# Index_Registers_-_1_1.net
KiCad netlist of a schematic drawn in EAGLE
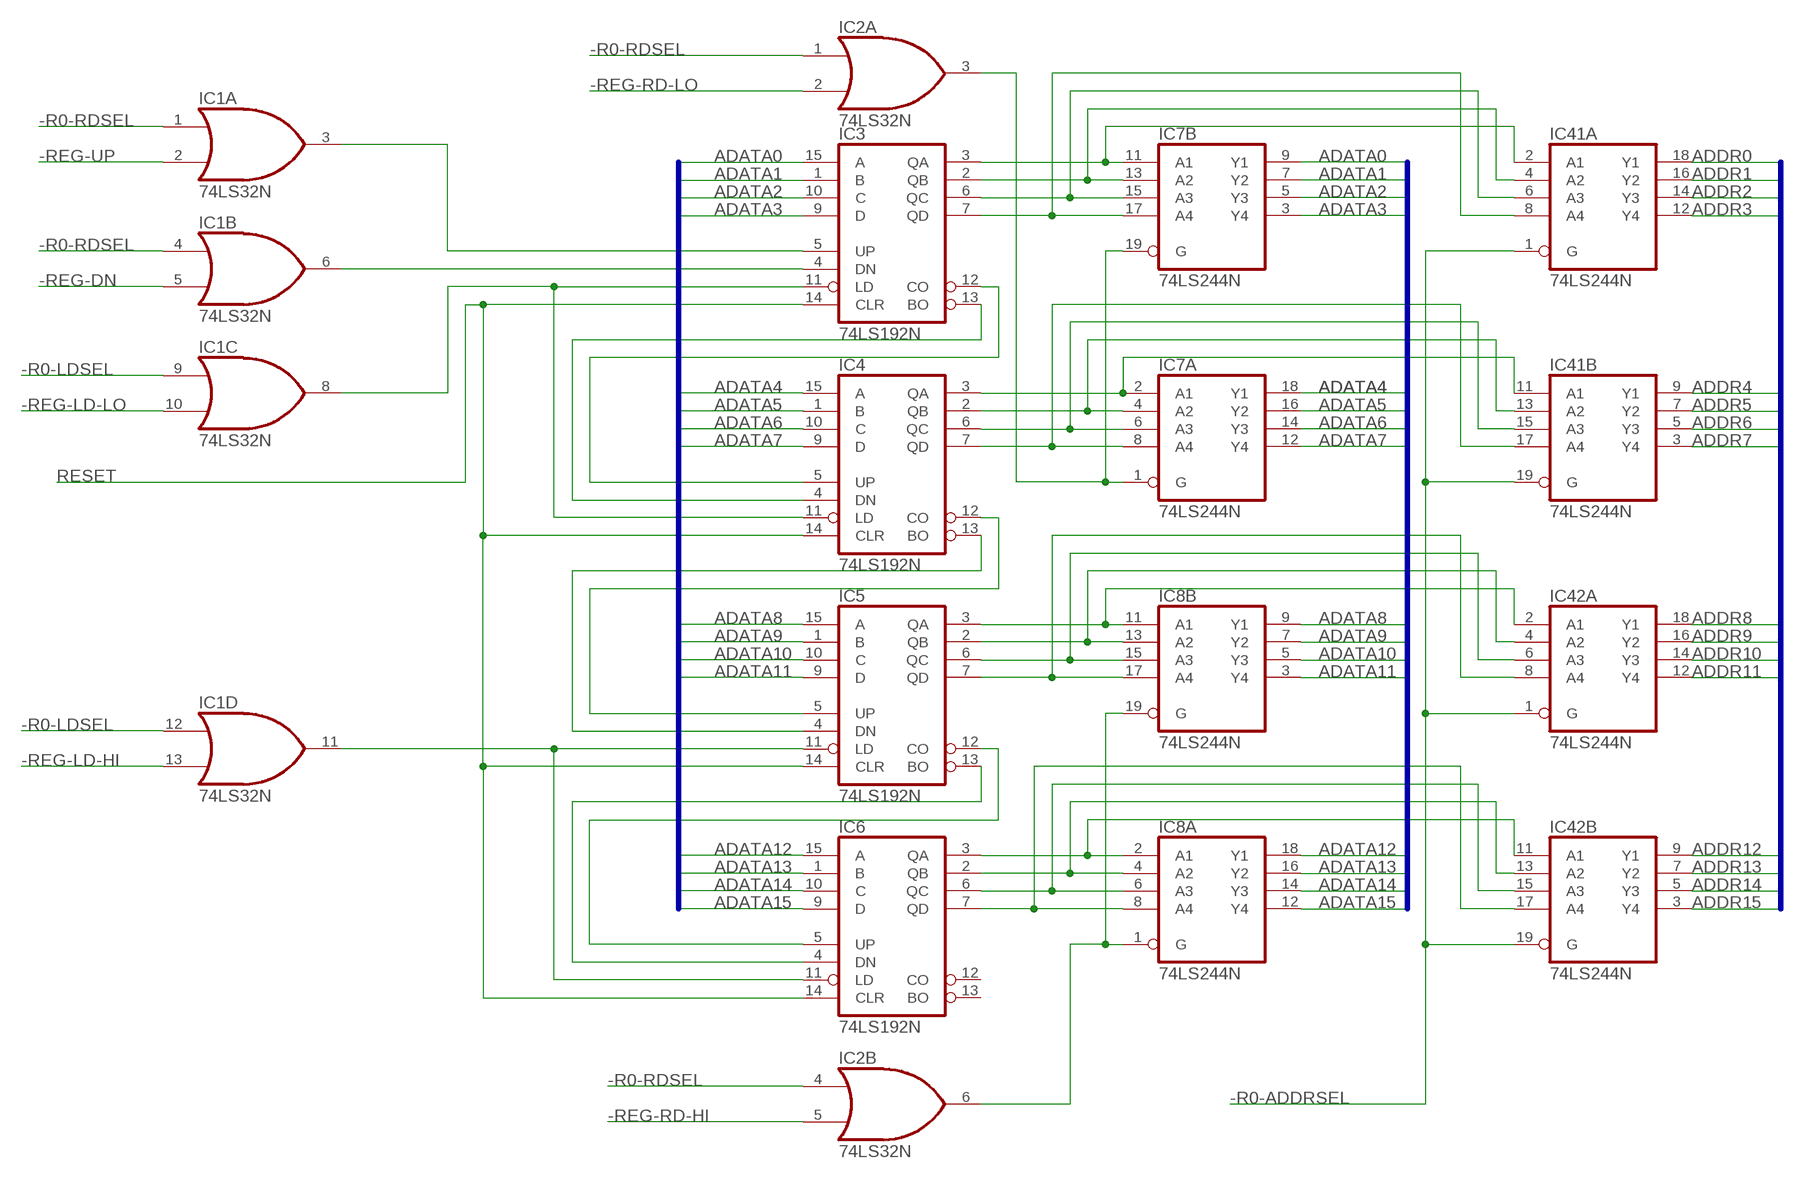
[diagram p0: schematic, sheet 1]
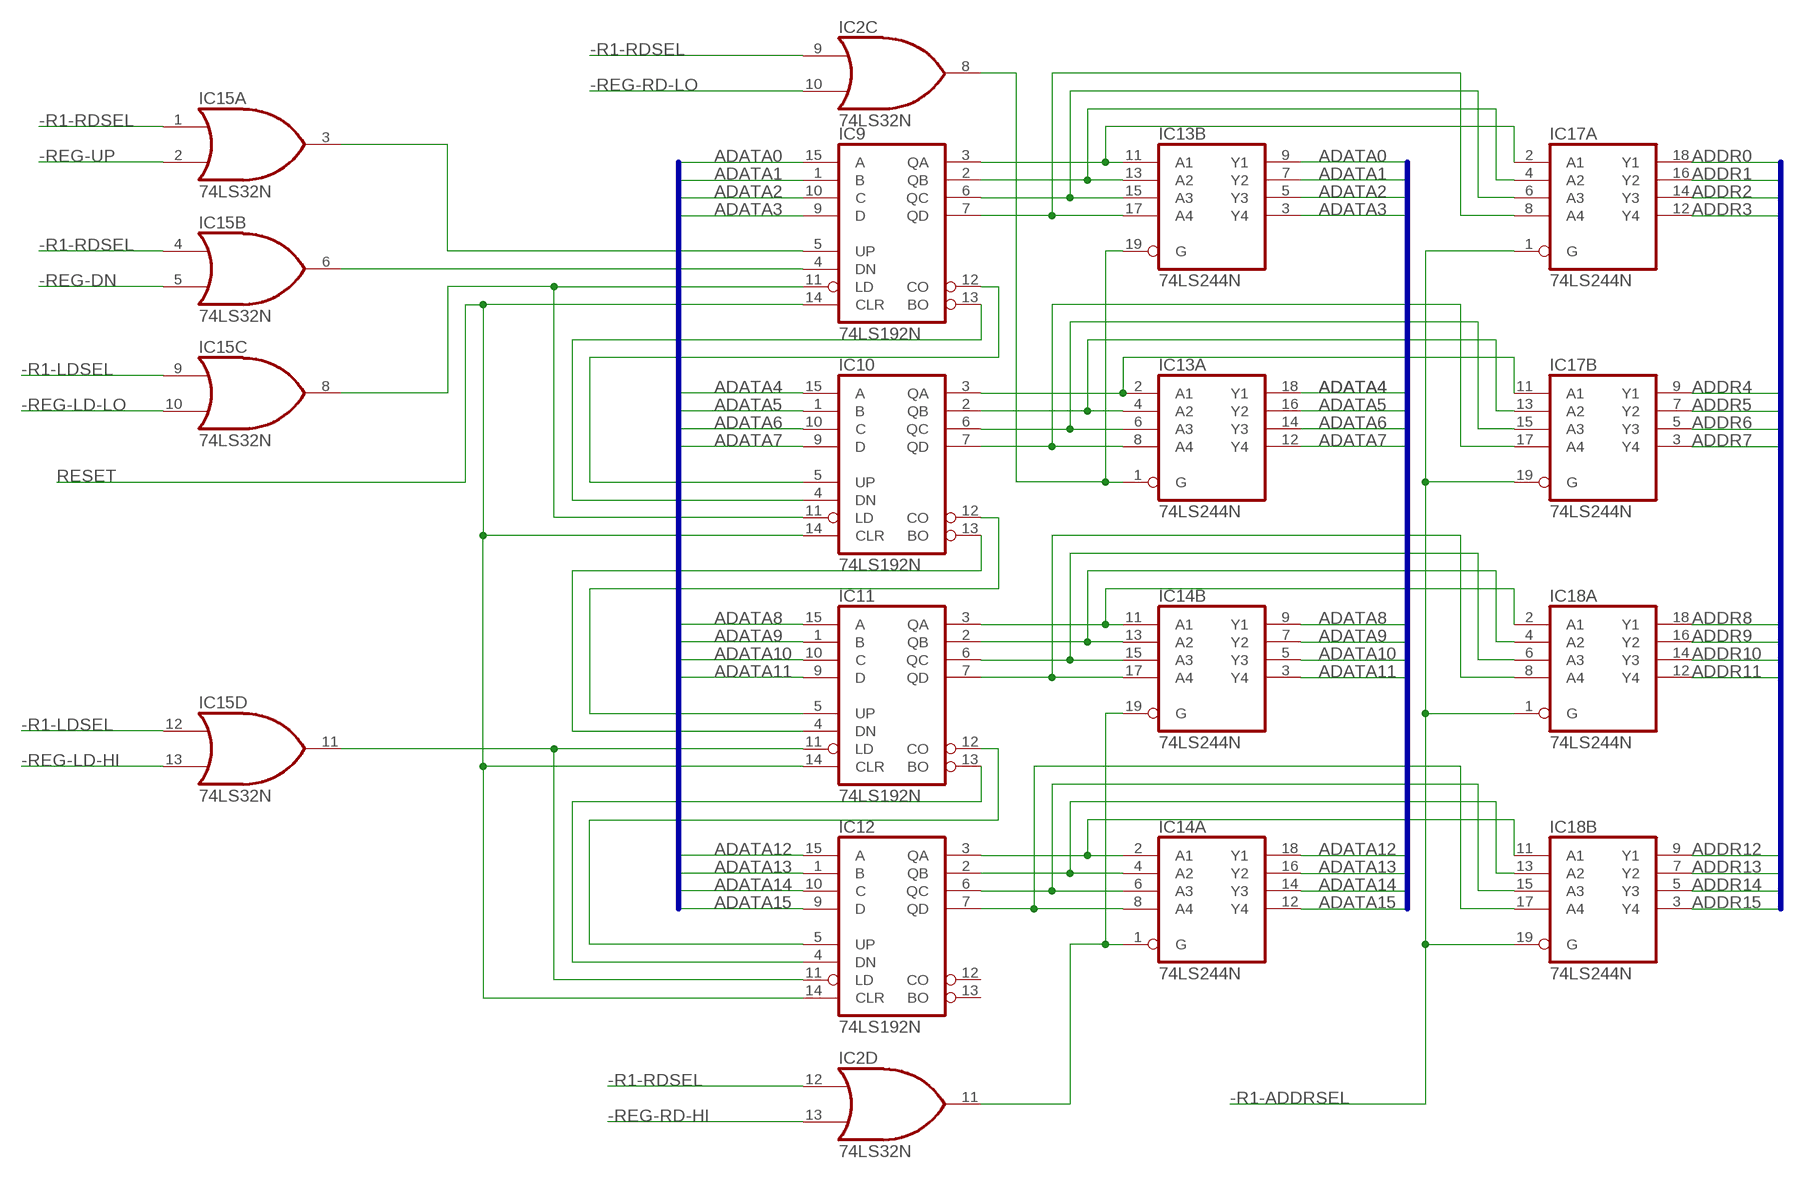
[diagram p1: schematic, sheet 2]
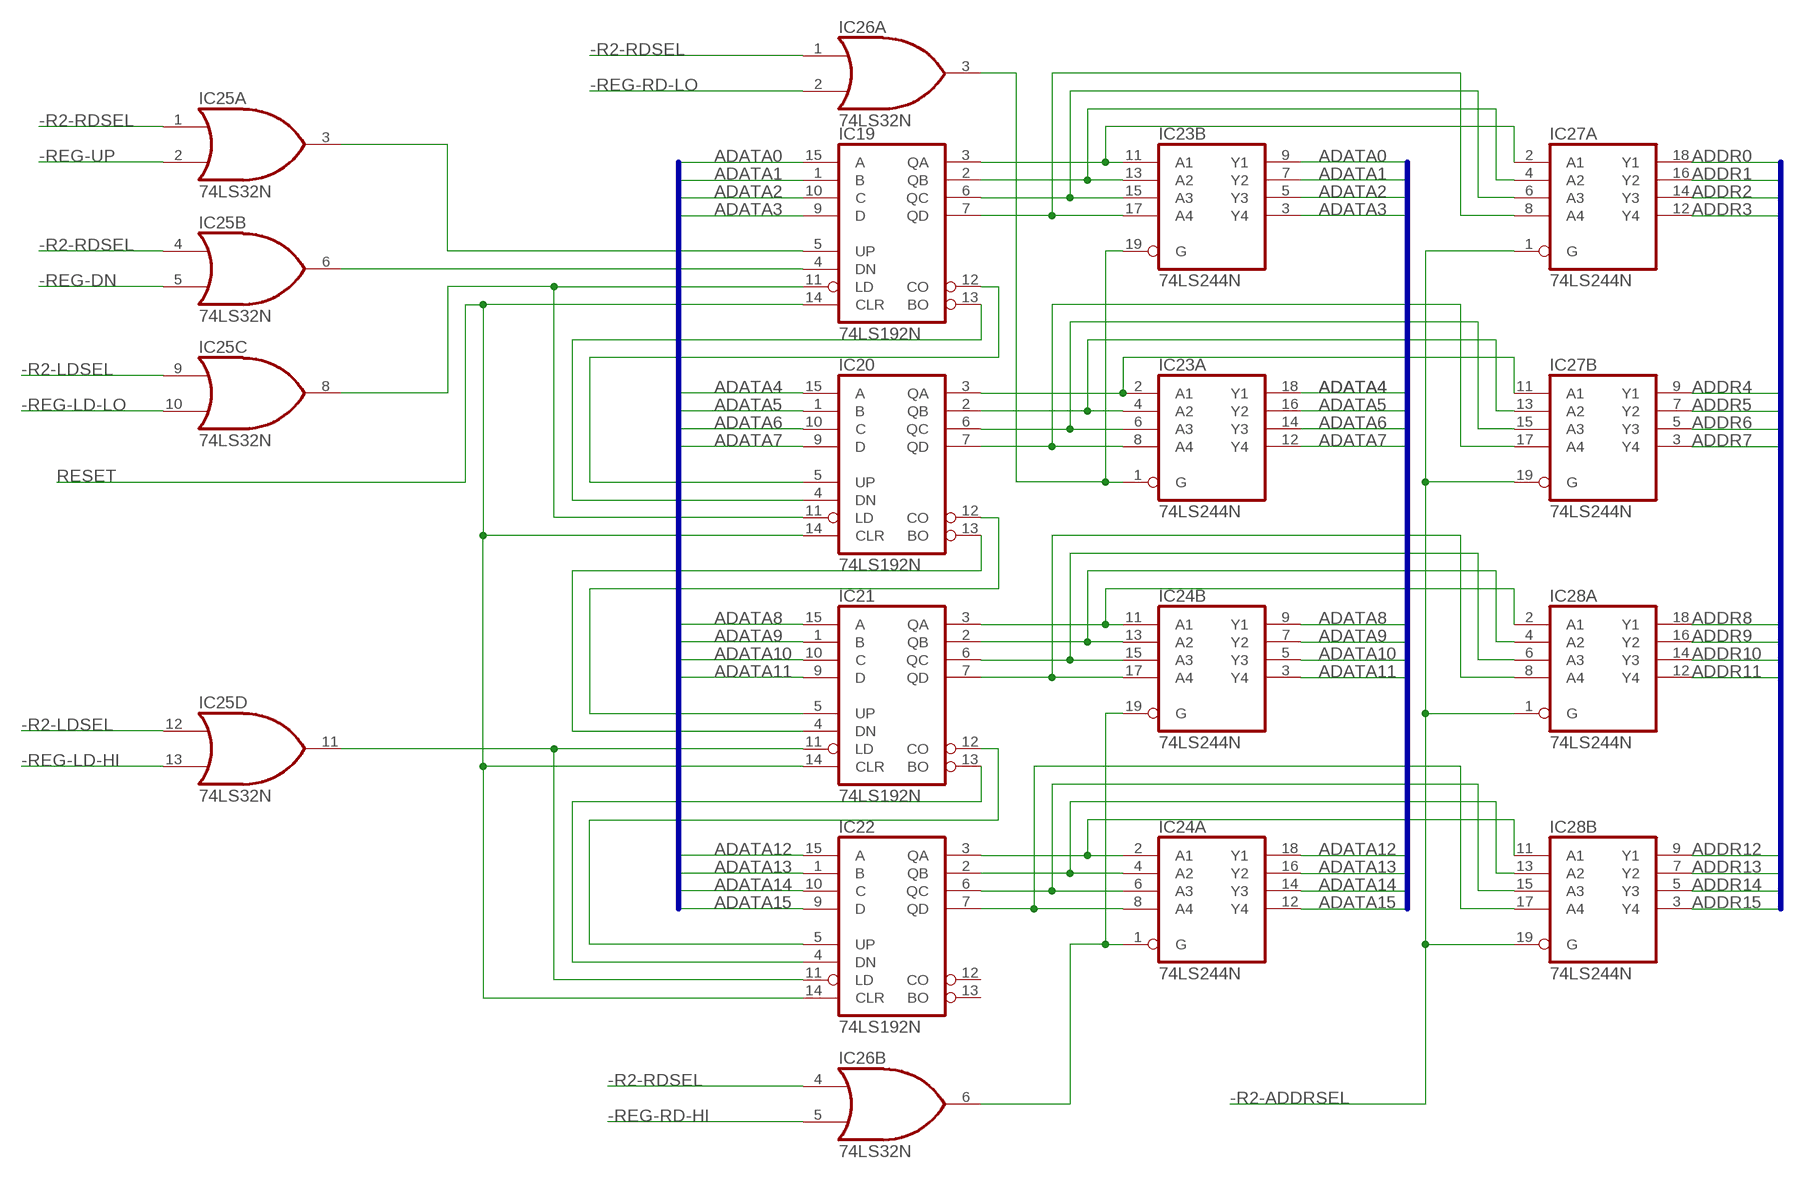
[diagram p2: schematic, sheet 3]
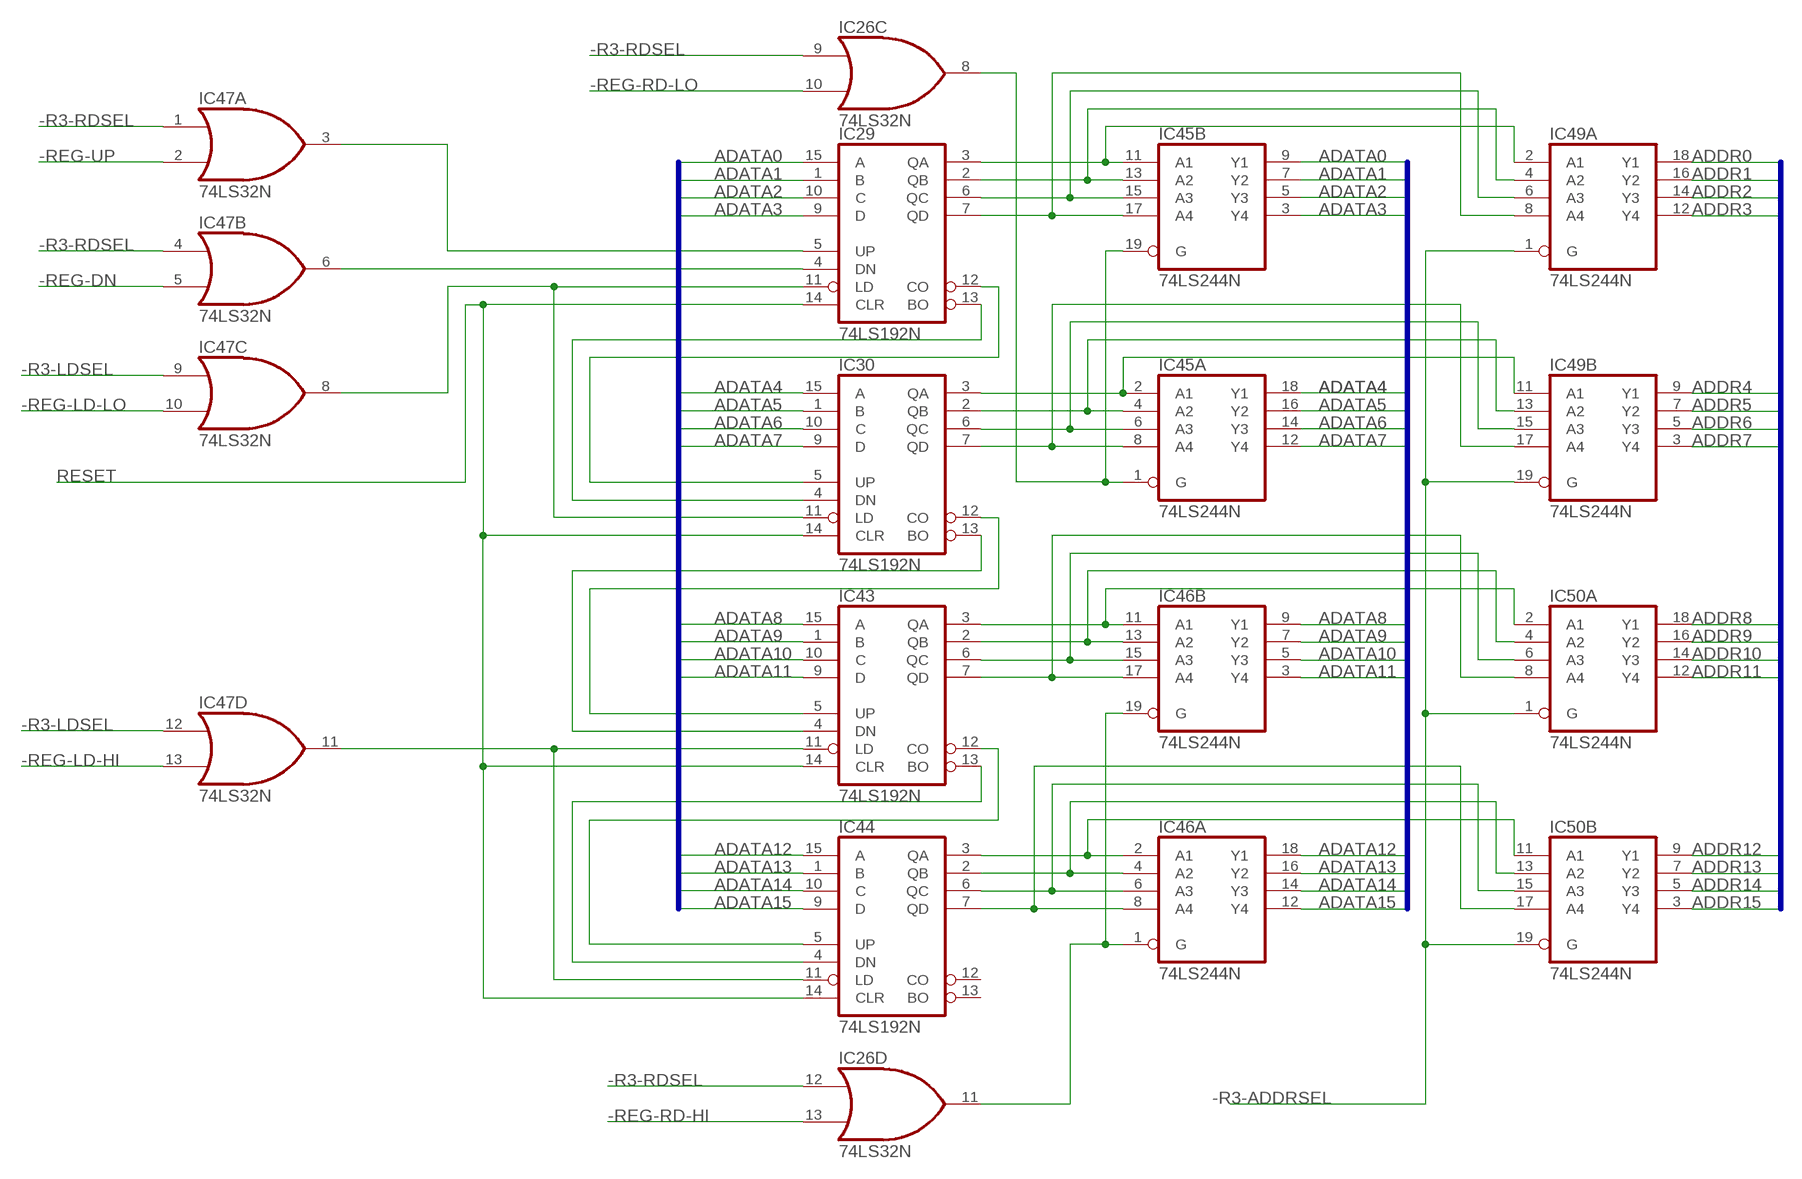
[diagram p3: schematic, sheet 4]
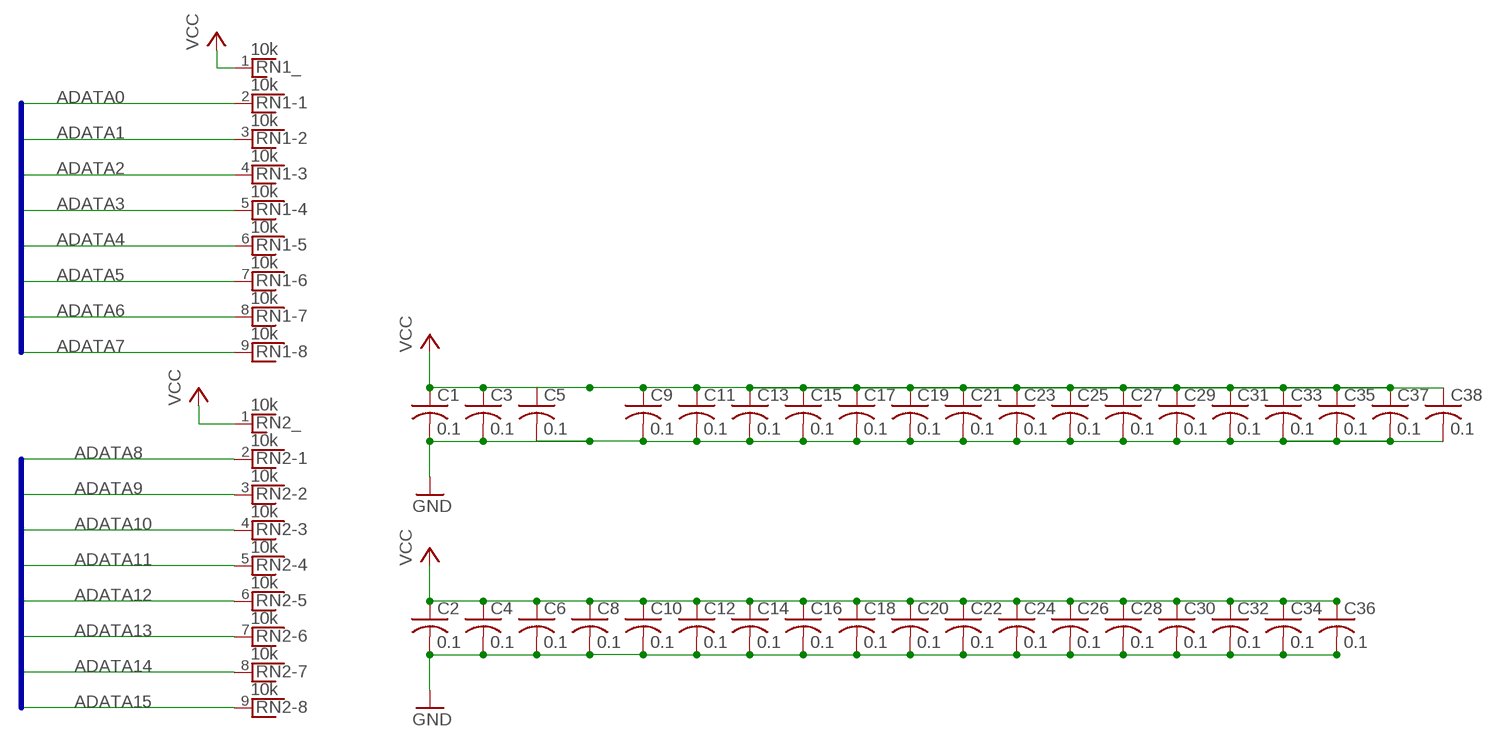
[diagram p4: schematic, sheet 5]
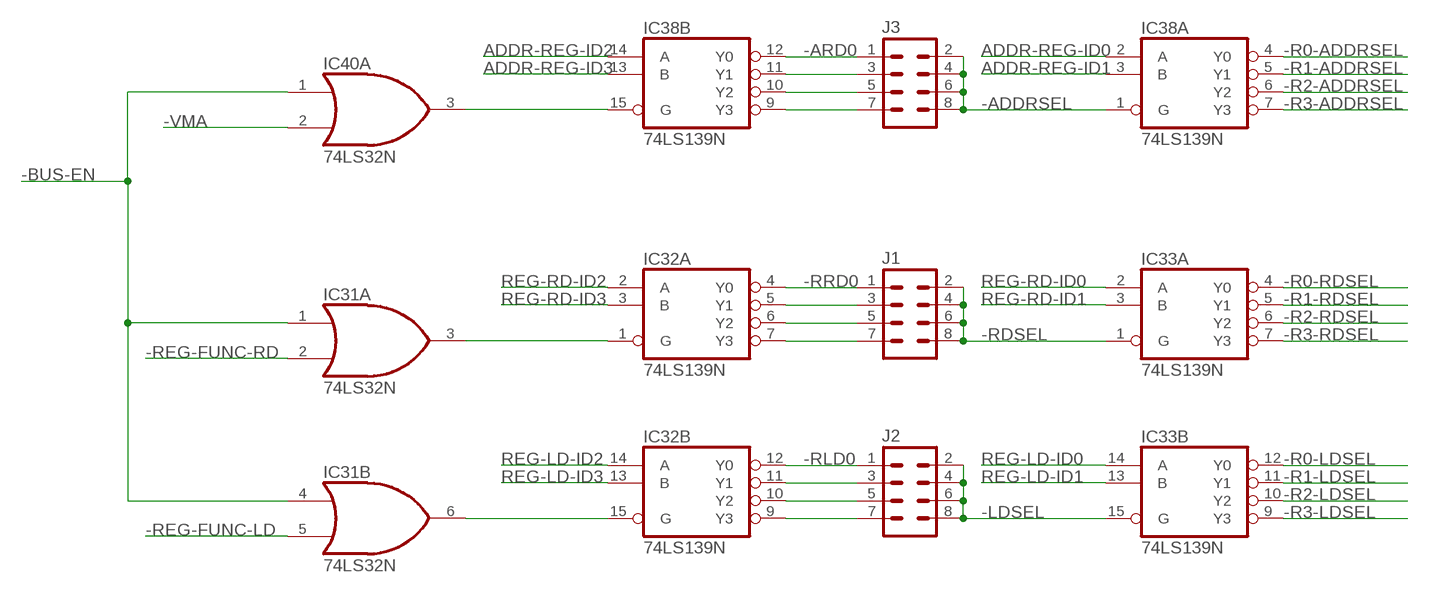
[diagram p5: schematic, sheet 6]
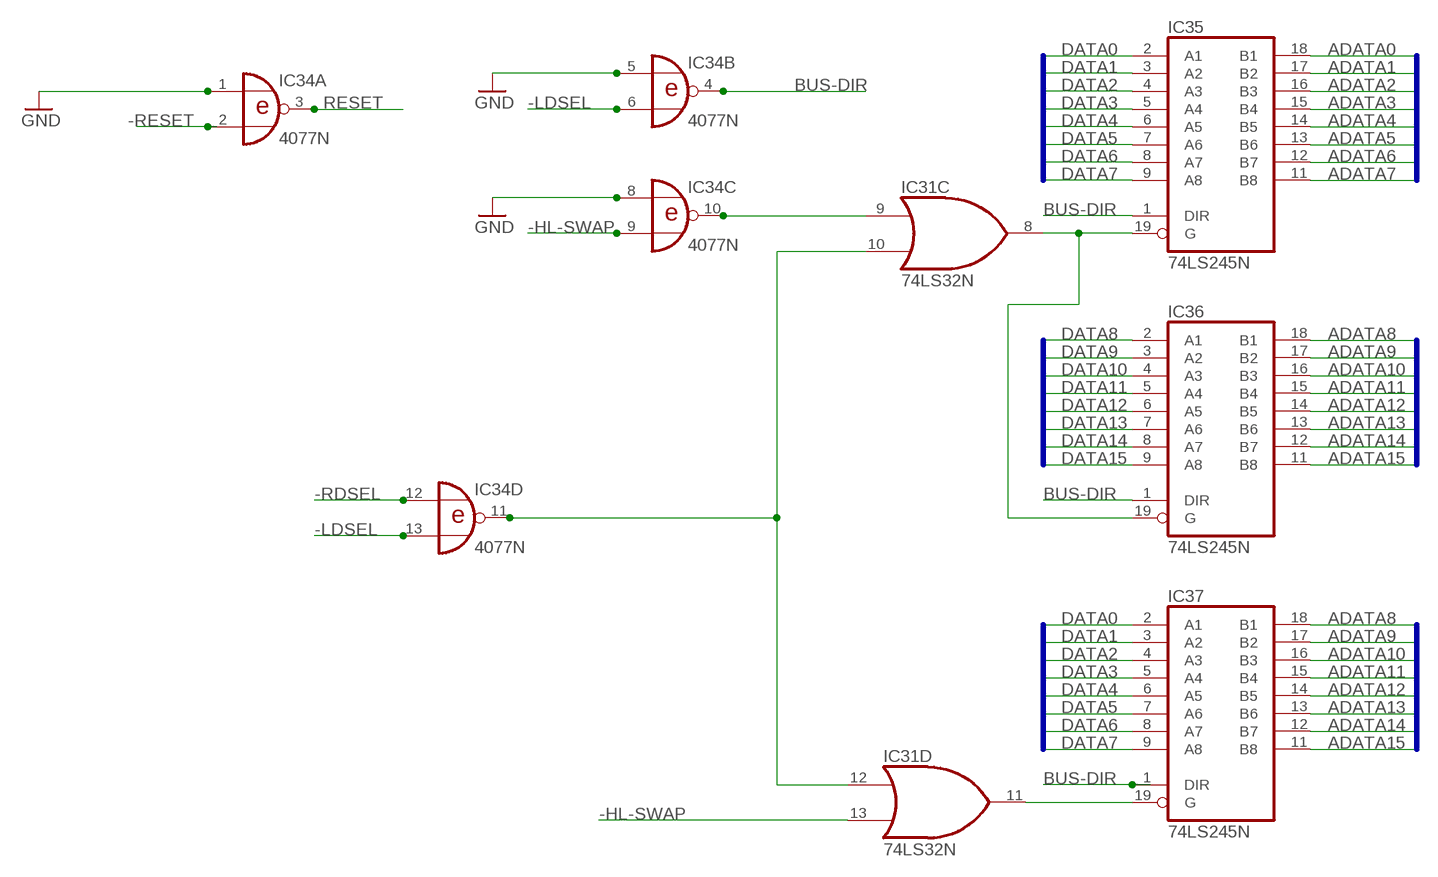
[diagram p6: schematic, sheet 7]
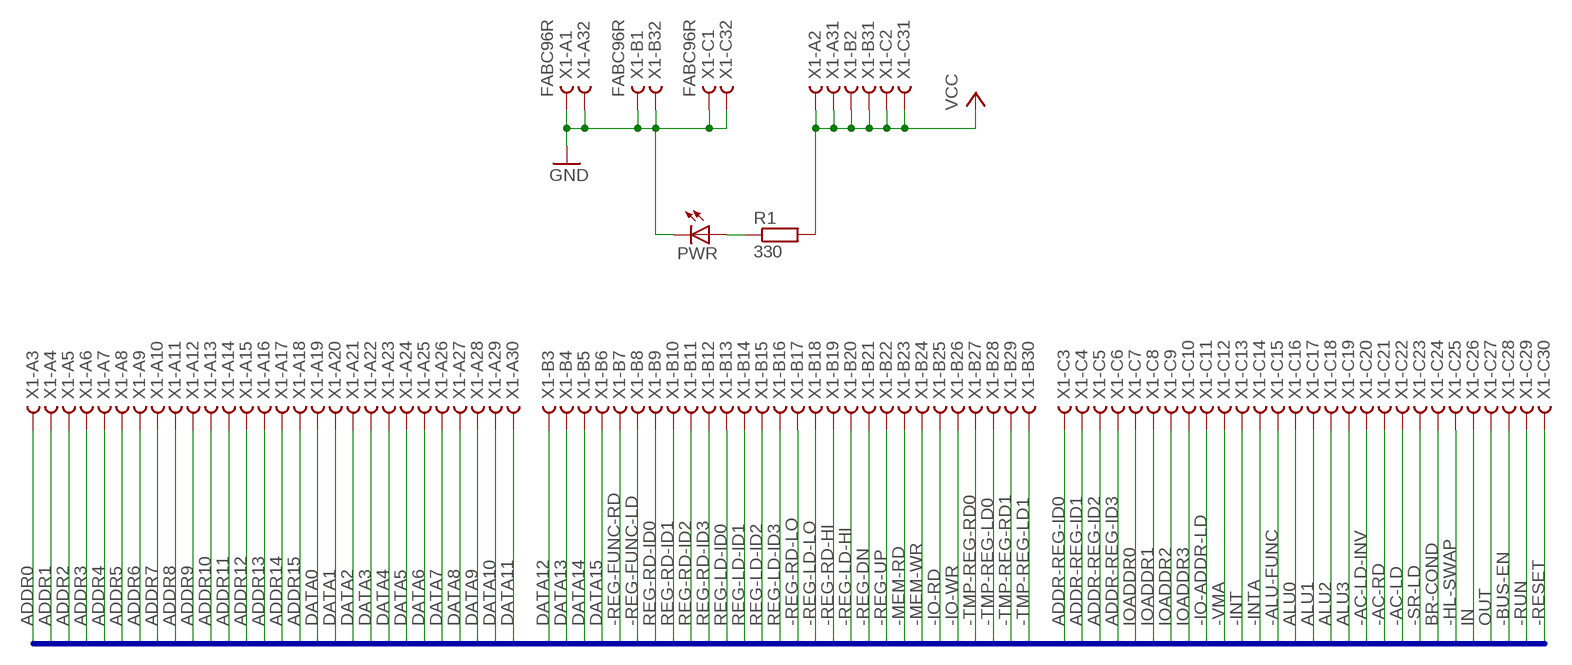
[diagram p7: schematic, sheet 8]

(export (version "E")
  (design (tool "Eeschema 10.0.6"))
  (components
    (comp (ref "IC1")
      (value "74LS32N")
      (footprint "eagle-import:DIL14")
      (libsource (lib "eagle-import") (part "7432NLS"))
    )
    (comp (ref "IC2")
      (value "74LS32N")
      (footprint "eagle-import:DIL14")
      (libsource (lib "eagle-import") (part "7432NLS"))
    )
    (comp (ref "IC3")
      (value "74LS192N")
      (footprint "eagle-import:DIL16")
      (libsource (lib "eagle-import") (part "74192NLS"))
    )
    (comp (ref "IC4")
      (value "74LS192N")
      (footprint "eagle-import:DIL16")
      (libsource (lib "eagle-import") (part "74192NLS"))
    )
    (comp (ref "IC5")
      (value "74LS192N")
      (footprint "eagle-import:DIL16")
      (libsource (lib "eagle-import") (part "74192NLS"))
    )
    (comp (ref "IC6")
      (value "74LS192N")
      (footprint "eagle-import:DIL16")
      (libsource (lib "eagle-import") (part "74192NLS"))
    )
    (comp (ref "IC7")
      (value "74LS244N")
      (footprint "eagle-import:DIL20")
      (libsource (lib "eagle-import") (part "74xx-us_74244NLS"))
    )
    (comp (ref "IC8")
      (value "74LS244N")
      (footprint "eagle-import:DIL20")
      (libsource (lib "eagle-import") (part "74xx-us_74244NLS"))
    )
    (comp (ref "IC41")
      (value "74LS244N")
      (footprint "eagle-import:DIL20")
      (libsource (lib "eagle-import") (part "74xx-us_88_74244NLS"))
    )
    (comp (ref "IC42")
      (value "74LS244N")
      (footprint "eagle-import:DIL20")
      (libsource (lib "eagle-import") (part "74xx-us_88_74244NLS"))
    )
    (comp (ref "IC9")
      (value "74LS192N")
      (footprint "eagle-import:DIL16")
      (libsource (lib "eagle-import") (part "74192NLS"))
    )
    (comp (ref "IC10")
      (value "74LS192N")
      (footprint "eagle-import:DIL16")
      (libsource (lib "eagle-import") (part "74192NLS"))
    )
    (comp (ref "IC11")
      (value "74LS192N")
      (footprint "eagle-import:DIL16")
      (libsource (lib "eagle-import") (part "74192NLS"))
    )
    (comp (ref "IC12")
      (value "74LS192N")
      (footprint "eagle-import:DIL16")
      (libsource (lib "eagle-import") (part "74192NLS"))
    )
    (comp (ref "IC13")
      (value "74LS244N")
      (footprint "eagle-import:DIL20")
      (libsource (lib "eagle-import") (part "74xx-us_74244NLS"))
    )
    (comp (ref "IC14")
      (value "74LS244N")
      (footprint "eagle-import:DIL20")
      (libsource (lib "eagle-import") (part "74xx-us_74244NLS"))
    )
    (comp (ref "IC15")
      (value "74LS32N")
      (footprint "eagle-import:DIL14")
      (libsource (lib "eagle-import") (part "7432NLS"))
    )
    (comp (ref "IC17")
      (value "74LS244N")
      (footprint "eagle-import:DIL20")
      (libsource (lib "eagle-import") (part "74xx-us_88_74244NLS"))
    )
    (comp (ref "IC18")
      (value "74LS244N")
      (footprint "eagle-import:DIL20")
      (libsource (lib "eagle-import") (part "74xx-us_88_74244NLS"))
    )
    (comp (ref "PWR")
      (value "LED5MM")
      (footprint "eagle-import:LED5MM")
      (libsource (lib "eagle-import") (part "LED5MM"))
    )
    (comp (ref "R1")
      (value "330")
      (footprint "eagle-import:0207_10")
      (libsource (lib "eagle-import") (part "R0207/10"))
    )
    (comp (ref "X1")
      (value "FABC96R")
      (footprint "eagle-import:FABC96R")
      (libsource (lib "eagle-import") (part "FABC96R"))
    )
    (comp (ref "IC31")
      (value "74LS32N")
      (footprint "eagle-import:DIL14")
      (libsource (lib "eagle-import") (part "7432NLS"))
    )
    (comp (ref "IC34")
      (value "4077N")
      (footprint "eagle-import:DIL14")
      (libsource (lib "eagle-import") (part "4077N"))
    )
    (comp (ref "IC35")
      (value "74LS245N")
      (footprint "eagle-import:DIL20")
      (libsource (lib "eagle-import") (part "74245NLS"))
    )
    (comp (ref "IC36")
      (value "74LS245N")
      (footprint "eagle-import:DIL20")
      (libsource (lib "eagle-import") (part "74245NLS"))
    )
    (comp (ref "IC37")
      (value "74LS245N")
      (footprint "eagle-import:DIL20")
      (libsource (lib "eagle-import") (part "74245NLS"))
    )
    (comp (ref "IC19")
      (value "74LS192N")
      (footprint "eagle-import:DIL16")
      (libsource (lib "eagle-import") (part "74192NLS"))
    )
    (comp (ref "IC20")
      (value "74LS192N")
      (footprint "eagle-import:DIL16")
      (libsource (lib "eagle-import") (part "74192NLS"))
    )
    (comp (ref "IC21")
      (value "74LS192N")
      (footprint "eagle-import:DIL16")
      (libsource (lib "eagle-import") (part "74192NLS"))
    )
    (comp (ref "IC22")
      (value "74LS192N")
      (footprint "eagle-import:DIL16")
      (libsource (lib "eagle-import") (part "74192NLS"))
    )
    (comp (ref "IC23")
      (value "74LS244N")
      (footprint "eagle-import:DIL20")
      (libsource (lib "eagle-import") (part "74xx-us_74244NLS"))
    )
    (comp (ref "IC24")
      (value "74LS244N")
      (footprint "eagle-import:DIL20")
      (libsource (lib "eagle-import") (part "74xx-us_74244NLS"))
    )
    (comp (ref "IC25")
      (value "74LS32N")
      (footprint "eagle-import:DIL14")
      (libsource (lib "eagle-import") (part "7432NLS"))
    )
    (comp (ref "IC26")
      (value "74LS32N")
      (footprint "eagle-import:DIL14")
      (libsource (lib "eagle-import") (part "7432NLS"))
    )
    (comp (ref "IC27")
      (value "74LS244N")
      (footprint "eagle-import:DIL20")
      (libsource (lib "eagle-import") (part "74xx-us_88_74244NLS"))
    )
    (comp (ref "IC28")
      (value "74LS244N")
      (footprint "eagle-import:DIL20")
      (libsource (lib "eagle-import") (part "74xx-us_88_74244NLS"))
    )
    (comp (ref "IC32")
      (value "74LS139N")
      (footprint "eagle-import:DIL16")
      (libsource (lib "eagle-import") (part "74139NLS"))
    )
    (comp (ref "IC33")
      (value "74LS139N")
      (footprint "eagle-import:DIL16")
      (libsource (lib "eagle-import") (part "74139NLS"))
    )
    (comp (ref "IC38")
      (value "74LS139N")
      (footprint "eagle-import:DIL16")
      (libsource (lib "eagle-import") (part "74139NLS"))
    )
    (comp (ref "IC40")
      (value "74LS32N")
      (footprint "eagle-import:DIL14")
      (libsource (lib "eagle-import") (part "7432NLS"))
    )
    (comp (ref "J1")
      (value "M04X2")
      (footprint "eagle-import:2X4")
      (libsource (lib "eagle-import") (part "M04X2"))
    )
    (comp (ref "J2")
      (value "M04X2")
      (footprint "eagle-import:2X4")
      (libsource (lib "eagle-import") (part "M04X2"))
    )
    (comp (ref "J3")
      (value "M04X2")
      (footprint "eagle-import:2X4")
      (libsource (lib "eagle-import") (part "M04X2"))
    )
    (comp (ref "IC29")
      (value "74LS192N")
      (footprint "eagle-import:DIL16")
      (libsource (lib "eagle-import") (part "74192NLS"))
    )
    (comp (ref "IC30")
      (value "74LS192N")
      (footprint "eagle-import:DIL16")
      (libsource (lib "eagle-import") (part "74192NLS"))
    )
    (comp (ref "IC43")
      (value "74LS192N")
      (footprint "eagle-import:DIL16")
      (libsource (lib "eagle-import") (part "74192NLS"))
    )
    (comp (ref "IC44")
      (value "74LS192N")
      (footprint "eagle-import:DIL16")
      (libsource (lib "eagle-import") (part "74192NLS"))
    )
    (comp (ref "IC45")
      (value "74LS244N")
      (footprint "eagle-import:DIL20")
      (libsource (lib "eagle-import") (part "74xx-us_74244NLS"))
    )
    (comp (ref "IC46")
      (value "74LS244N")
      (footprint "eagle-import:DIL20")
      (libsource (lib "eagle-import") (part "74xx-us_74244NLS"))
    )
    (comp (ref "IC47")
      (value "74LS32N")
      (footprint "eagle-import:DIL14")
      (libsource (lib "eagle-import") (part "7432NLS"))
    )
    (comp (ref "IC49")
      (value "74LS244N")
      (footprint "eagle-import:DIL20")
      (libsource (lib "eagle-import") (part "74xx-us_88_74244NLS"))
    )
    (comp (ref "IC50")
      (value "74LS244N")
      (footprint "eagle-import:DIL20")
      (libsource (lib "eagle-import") (part "74xx-us_88_74244NLS"))
    )
    (comp (ref "C1")
      (value "0.1")
      (footprint "eagle-import:C025-040X050")
      (libsource (lib "eagle-import") (part "C-US025-040X050"))
    )
    (comp (ref "C2")
      (value "0.1")
      (footprint "eagle-import:C025-040X050")
      (libsource (lib "eagle-import") (part "C-US025-040X050"))
    )
    (comp (ref "C3")
      (value "0.1")
      (footprint "eagle-import:C025-040X050")
      (libsource (lib "eagle-import") (part "C-US025-040X050"))
    )
    (comp (ref "C4")
      (value "0.1")
      (footprint "eagle-import:C025-040X050")
      (libsource (lib "eagle-import") (part "C-US025-040X050"))
    )
    (comp (ref "C5")
      (value "0.1")
      (footprint "eagle-import:C025-040X050")
      (libsource (lib "eagle-import") (part "C-US025-040X050"))
    )
    (comp (ref "C6")
      (value "0.1")
      (footprint "eagle-import:C025-040X050")
      (libsource (lib "eagle-import") (part "C-US025-040X050"))
    )
    (comp (ref "C8")
      (value "0.1")
      (footprint "eagle-import:C025-040X050")
      (libsource (lib "eagle-import") (part "C-US025-040X050"))
    )
    (comp (ref "C9")
      (value "0.1")
      (footprint "eagle-import:C025-040X050")
      (libsource (lib "eagle-import") (part "C-US025-040X050"))
    )
    (comp (ref "C10")
      (value "0.1")
      (footprint "eagle-import:C025-040X050")
      (libsource (lib "eagle-import") (part "C-US025-040X050"))
    )
    (comp (ref "C11")
      (value "0.1")
      (footprint "eagle-import:C025-040X050")
      (libsource (lib "eagle-import") (part "C-US025-040X050"))
    )
    (comp (ref "C12")
      (value "0.1")
      (footprint "eagle-import:C025-040X050")
      (libsource (lib "eagle-import") (part "C-US025-040X050"))
    )
    (comp (ref "C13")
      (value "0.1")
      (footprint "eagle-import:C025-040X050")
      (libsource (lib "eagle-import") (part "C-US025-040X050"))
    )
    (comp (ref "C14")
      (value "0.1")
      (footprint "eagle-import:C025-040X050")
      (libsource (lib "eagle-import") (part "C-US025-040X050"))
    )
    (comp (ref "C15")
      (value "0.1")
      (footprint "eagle-import:C025-040X050")
      (libsource (lib "eagle-import") (part "C-US025-040X050"))
    )
    (comp (ref "C16")
      (value "0.1")
      (footprint "eagle-import:C025-040X050")
      (libsource (lib "eagle-import") (part "C-US025-040X050"))
    )
    (comp (ref "C17")
      (value "0.1")
      (footprint "eagle-import:C025-040X050")
      (libsource (lib "eagle-import") (part "C-US025-040X050"))
    )
    (comp (ref "C18")
      (value "0.1")
      (footprint "eagle-import:C025-040X050")
      (libsource (lib "eagle-import") (part "C-US025-040X050"))
    )
    (comp (ref "C19")
      (value "0.1")
      (footprint "eagle-import:C025-040X050")
      (libsource (lib "eagle-import") (part "C-US025-040X050"))
    )
    (comp (ref "C20")
      (value "0.1")
      (footprint "eagle-import:C025-040X050")
      (libsource (lib "eagle-import") (part "C-US025-040X050"))
    )
    (comp (ref "C21")
      (value "0.1")
      (footprint "eagle-import:C025-040X050")
      (libsource (lib "eagle-import") (part "C-US025-040X050"))
    )
    (comp (ref "C22")
      (value "0.1")
      (footprint "eagle-import:C025-040X050")
      (libsource (lib "eagle-import") (part "C-US025-040X050"))
    )
    (comp (ref "C23")
      (value "0.1")
      (footprint "eagle-import:C025-040X050")
      (libsource (lib "eagle-import") (part "C-US025-040X050"))
    )
    (comp (ref "C24")
      (value "0.1")
      (footprint "eagle-import:C025-040X050")
      (libsource (lib "eagle-import") (part "C-US025-040X050"))
    )
    (comp (ref "C25")
      (value "0.1")
      (footprint "eagle-import:C025-040X050")
      (libsource (lib "eagle-import") (part "C-US025-040X050"))
    )
    (comp (ref "C26")
      (value "0.1")
      (footprint "eagle-import:C025-040X050")
      (libsource (lib "eagle-import") (part "C-US025-040X050"))
    )
    (comp (ref "C27")
      (value "0.1")
      (footprint "eagle-import:C025-040X050")
      (libsource (lib "eagle-import") (part "C-US025-040X050"))
    )
    (comp (ref "C28")
      (value "0.1")
      (footprint "eagle-import:C025-040X050")
      (libsource (lib "eagle-import") (part "C-US025-040X050"))
    )
    (comp (ref "C29")
      (value "0.1")
      (footprint "eagle-import:C025-040X050")
      (libsource (lib "eagle-import") (part "C-US025-040X050"))
    )
    (comp (ref "C30")
      (value "0.1")
      (footprint "eagle-import:C025-040X050")
      (libsource (lib "eagle-import") (part "C-US025-040X050"))
    )
    (comp (ref "C31")
      (value "0.1")
      (footprint "eagle-import:C025-040X050")
      (libsource (lib "eagle-import") (part "C-US025-040X050"))
    )
    (comp (ref "C32")
      (value "0.1")
      (footprint "eagle-import:C025-040X050")
      (libsource (lib "eagle-import") (part "C-US025-040X050"))
    )
    (comp (ref "C33")
      (value "0.1")
      (footprint "eagle-import:C025-040X050")
      (libsource (lib "eagle-import") (part "C-US025-040X050"))
    )
    (comp (ref "C34")
      (value "0.1")
      (footprint "eagle-import:C025-040X050")
      (libsource (lib "eagle-import") (part "C-US025-040X050"))
    )
    (comp (ref "C35")
      (value "0.1")
      (footprint "eagle-import:C025-040X050")
      (libsource (lib "eagle-import") (part "C-US025-040X050"))
    )
    (comp (ref "C36")
      (value "0.1")
      (footprint "eagle-import:C025-040X050")
      (libsource (lib "eagle-import") (part "C-US025-040X050"))
    )
    (comp (ref "C37")
      (value "0.1")
      (footprint "eagle-import:C025-040X050")
      (libsource (lib "eagle-import") (part "C-US025-040X050"))
    )
    (comp (ref "C38")
      (value "0.1")
      (footprint "eagle-import:C025-040X050")
      (libsource (lib "eagle-import") (part "C-US025-040X050"))
    )
    (comp (ref "RN1")
      (value "10k")
      (footprint "eagle-import:RN-9")
      (libsource (lib "eagle-import") (part "RNX8"))
    )
    (comp (ref "RN2")
      (value "10k")
      (footprint "eagle-import:RN-9")
      (libsource (lib "eagle-import") (part "RNX8"))
    )
  )
  (nets
    (net (code "1") (name "-AC-LD") (class "Default")
      (node (ref "X1") (pin "C22") (pinfunction "B_C22") (pintype "passive"))
    )
    (net (code "2") (name "-AC-LD-INV") (class "Default")
      (node (ref "X1") (pin "C20") (pinfunction "B_C20") (pintype "passive"))
    )
    (net (code "3") (name "-AC-RD") (class "Default")
      (node (ref "X1") (pin "C21") (pinfunction "B_C21") (pintype "passive"))
    )
    (net (code "4") (name "-ADDRSEL") (class "Default")
      (node (ref "IC38") (pin "1") (pinfunction "G_1") (pintype "input"))
      (node (ref "J3") (pin "2") (pinfunction "2_2") (pintype "passive"))
      (node (ref "J3") (pin "4") (pinfunction "4_4") (pintype "passive"))
      (node (ref "J3") (pin "6") (pinfunction "6_6") (pintype "passive"))
      (node (ref "J3") (pin "8") (pinfunction "8_8") (pintype "passive"))
    )
    (net (code "5") (name "-ALU-FUNC") (class "Default")
      (node (ref "X1") (pin "C15") (pinfunction "B_C15") (pintype "passive"))
    )
    (net (code "6") (name "-ARD0") (class "Default")
      (node (ref "IC38") (pin "12") (pinfunction "Y0_12") (pintype "output"))
      (node (ref "J3") (pin "1") (pinfunction "1_1") (pintype "passive"))
    )
    (net (code "7") (name "-BUS-EN") (class "Default")
      (node (ref "IC31") (pin "1") (pinfunction "I0_1") (pintype "input"))
      (node (ref "IC31") (pin "4") (pinfunction "I0_4") (pintype "input"))
      (node (ref "IC40") (pin "1") (pinfunction "I0_1") (pintype "input"))
      (node (ref "X1") (pin "C28") (pinfunction "B_C28") (pintype "passive"))
    )
    (net (code "8") (name "-HL-SWAP") (class "Default")
      (node (ref "IC31") (pin "13") (pinfunction "I1_13") (pintype "input"))
      (node (ref "IC34") (pin "9") (pinfunction "I1_9") (pintype "input"))
      (node (ref "X1") (pin "C25") (pinfunction "B_C25") (pintype "passive"))
    )
    (net (code "9") (name "-INT") (class "Default")
      (node (ref "X1") (pin "C13") (pinfunction "B_C13") (pintype "passive"))
    )
    (net (code "10") (name "-INTA") (class "Default")
      (node (ref "X1") (pin "C14") (pinfunction "B_C14") (pintype "passive"))
    )
    (net (code "11") (name "-IO-ADDR-LD") (class "Default")
      (node (ref "X1") (pin "C11") (pinfunction "B_C11") (pintype "passive"))
    )
    (net (code "12") (name "-IO-RD") (class "Default")
      (node (ref "X1") (pin "B25") (pinfunction "B_B25") (pintype "passive"))
    )
    (net (code "13") (name "-IO-WR") (class "Default")
      (node (ref "X1") (pin "B26") (pinfunction "B_B26") (pintype "passive"))
    )
    (net (code "14") (name "-LDSEL") (class "Default")
      (node (ref "IC33") (pin "15") (pinfunction "G_15") (pintype "input"))
      (node (ref "IC34") (pin "13") (pinfunction "I1_13") (pintype "input"))
      (node (ref "IC34") (pin "6") (pinfunction "I1_6") (pintype "input"))
      (node (ref "J2") (pin "2") (pinfunction "2_2") (pintype "passive"))
      (node (ref "J2") (pin "4") (pinfunction "4_4") (pintype "passive"))
      (node (ref "J2") (pin "6") (pinfunction "6_6") (pintype "passive"))
      (node (ref "J2") (pin "8") (pinfunction "8_8") (pintype "passive"))
    )
    (net (code "15") (name "-MEM-RD") (class "Default")
      (node (ref "X1") (pin "B23") (pinfunction "B_B23") (pintype "passive"))
    )
    (net (code "16") (name "-MEM-WR") (class "Default")
      (node (ref "X1") (pin "B24") (pinfunction "B_B24") (pintype "passive"))
    )
    (net (code "17") (name "-R0-ADDRSEL") (class "Default")
      (node (ref "IC38") (pin "4") (pinfunction "Y0_4") (pintype "output"))
      (node (ref "IC41") (pin "1") (pinfunction "G_1") (pintype "input"))
      (node (ref "IC41") (pin "19") (pinfunction "G_19") (pintype "input"))
      (node (ref "IC42") (pin "1") (pinfunction "G_1") (pintype "input"))
      (node (ref "IC42") (pin "19") (pinfunction "G_19") (pintype "input"))
    )
    (net (code "18") (name "-R0-LDSEL") (class "Default")
      (node (ref "IC1") (pin "12") (pinfunction "I0_12") (pintype "input"))
      (node (ref "IC1") (pin "9") (pinfunction "I0_9") (pintype "input"))
      (node (ref "IC33") (pin "12") (pinfunction "Y0_12") (pintype "output"))
    )
    (net (code "19") (name "-R0-RDSEL") (class "Default")
      (node (ref "IC1") (pin "1") (pinfunction "I0_1") (pintype "input"))
      (node (ref "IC1") (pin "4") (pinfunction "I0_4") (pintype "input"))
      (node (ref "IC2") (pin "1") (pinfunction "I0_1") (pintype "input"))
      (node (ref "IC2") (pin "4") (pinfunction "I0_4") (pintype "input"))
      (node (ref "IC33") (pin "4") (pinfunction "Y0_4") (pintype "output"))
    )
    (net (code "20") (name "-R1-ADDRSEL") (class "Default")
      (node (ref "IC17") (pin "1") (pinfunction "G_1") (pintype "input"))
      (node (ref "IC17") (pin "19") (pinfunction "G_19") (pintype "input"))
      (node (ref "IC18") (pin "1") (pinfunction "G_1") (pintype "input"))
      (node (ref "IC18") (pin "19") (pinfunction "G_19") (pintype "input"))
      (node (ref "IC38") (pin "5") (pinfunction "Y1_5") (pintype "output"))
    )
    (net (code "21") (name "-R1-LDSEL") (class "Default")
      (node (ref "IC15") (pin "12") (pinfunction "I0_12") (pintype "input"))
      (node (ref "IC15") (pin "9") (pinfunction "I0_9") (pintype "input"))
      (node (ref "IC33") (pin "11") (pinfunction "Y1_11") (pintype "output"))
    )
    (net (code "22") (name "-R1-RDSEL") (class "Default")
      (node (ref "IC15") (pin "1") (pinfunction "I0_1") (pintype "input"))
      (node (ref "IC15") (pin "4") (pinfunction "I0_4") (pintype "input"))
      (node (ref "IC2") (pin "12") (pinfunction "I0_12") (pintype "input"))
      (node (ref "IC2") (pin "9") (pinfunction "I0_9") (pintype "input"))
      (node (ref "IC33") (pin "5") (pinfunction "Y1_5") (pintype "output"))
    )
    (net (code "23") (name "-R2-ADDRSEL") (class "Default")
      (node (ref "IC27") (pin "1") (pinfunction "G_1") (pintype "input"))
      (node (ref "IC27") (pin "19") (pinfunction "G_19") (pintype "input"))
      (node (ref "IC28") (pin "1") (pinfunction "G_1") (pintype "input"))
      (node (ref "IC28") (pin "19") (pinfunction "G_19") (pintype "input"))
      (node (ref "IC38") (pin "6") (pinfunction "Y2_6") (pintype "output"))
    )
    (net (code "24") (name "-R2-LDSEL") (class "Default")
      (node (ref "IC25") (pin "12") (pinfunction "I0_12") (pintype "input"))
      (node (ref "IC25") (pin "9") (pinfunction "I0_9") (pintype "input"))
      (node (ref "IC33") (pin "10") (pinfunction "Y2_10") (pintype "output"))
    )
    (net (code "25") (name "-R2-RDSEL") (class "Default")
      (node (ref "IC25") (pin "1") (pinfunction "I0_1") (pintype "input"))
      (node (ref "IC25") (pin "4") (pinfunction "I0_4") (pintype "input"))
      (node (ref "IC26") (pin "1") (pinfunction "I0_1") (pintype "input"))
      (node (ref "IC26") (pin "4") (pinfunction "I0_4") (pintype "input"))
      (node (ref "IC33") (pin "6") (pinfunction "Y2_6") (pintype "output"))
    )
    (net (code "26") (name "-R3-ADDRSEL") (class "Default")
      (node (ref "IC38") (pin "7") (pinfunction "Y3_7") (pintype "output"))
      (node (ref "IC49") (pin "1") (pinfunction "G_1") (pintype "input"))
      (node (ref "IC49") (pin "19") (pinfunction "G_19") (pintype "input"))
      (node (ref "IC50") (pin "1") (pinfunction "G_1") (pintype "input"))
      (node (ref "IC50") (pin "19") (pinfunction "G_19") (pintype "input"))
    )
    (net (code "27") (name "-R3-LDSEL") (class "Default")
      (node (ref "IC33") (pin "9") (pinfunction "Y3_9") (pintype "output"))
      (node (ref "IC47") (pin "12") (pinfunction "I0_12") (pintype "input"))
      (node (ref "IC47") (pin "9") (pinfunction "I0_9") (pintype "input"))
    )
    (net (code "28") (name "-R3-RDSEL") (class "Default")
      (node (ref "IC26") (pin "12") (pinfunction "I0_12") (pintype "input"))
      (node (ref "IC26") (pin "9") (pinfunction "I0_9") (pintype "input"))
      (node (ref "IC33") (pin "7") (pinfunction "Y3_7") (pintype "output"))
      (node (ref "IC47") (pin "1") (pinfunction "I0_1") (pintype "input"))
      (node (ref "IC47") (pin "4") (pinfunction "I0_4") (pintype "input"))
    )
    (net (code "29") (name "-RDSEL") (class "Default")
      (node (ref "IC33") (pin "1") (pinfunction "G_1") (pintype "input"))
      (node (ref "IC34") (pin "12") (pinfunction "I0_12") (pintype "input"))
      (node (ref "J1") (pin "2") (pinfunction "2_2") (pintype "passive"))
      (node (ref "J1") (pin "4") (pinfunction "4_4") (pintype "passive"))
      (node (ref "J1") (pin "6") (pinfunction "6_6") (pintype "passive"))
      (node (ref "J1") (pin "8") (pinfunction "8_8") (pintype "passive"))
    )
    (net (code "30") (name "-REG-DN") (class "Default")
      (node (ref "IC1") (pin "5") (pinfunction "I1_5") (pintype "input"))
      (node (ref "IC15") (pin "5") (pinfunction "I1_5") (pintype "input"))
      (node (ref "IC25") (pin "5") (pinfunction "I1_5") (pintype "input"))
      (node (ref "IC47") (pin "5") (pinfunction "I1_5") (pintype "input"))
      (node (ref "X1") (pin "B21") (pinfunction "B_B21") (pintype "passive"))
    )
    (net (code "31") (name "-REG-FUNC-LD") (class "Default")
      (node (ref "IC31") (pin "5") (pinfunction "I1_5") (pintype "input"))
      (node (ref "X1") (pin "B8") (pinfunction "B_B8") (pintype "passive"))
    )
    (net (code "32") (name "-REG-FUNC-RD") (class "Default")
      (node (ref "IC31") (pin "2") (pinfunction "I1_2") (pintype "input"))
      (node (ref "X1") (pin "B7") (pinfunction "B_B7") (pintype "passive"))
    )
    (net (code "33") (name "-REG-LD-HI") (class "Default")
      (node (ref "IC1") (pin "13") (pinfunction "I1_13") (pintype "input"))
      (node (ref "IC15") (pin "13") (pinfunction "I1_13") (pintype "input"))
      (node (ref "IC25") (pin "13") (pinfunction "I1_13") (pintype "input"))
      (node (ref "IC47") (pin "13") (pinfunction "I1_13") (pintype "input"))
      (node (ref "X1") (pin "B20") (pinfunction "B_B20") (pintype "passive"))
    )
    (net (code "34") (name "-REG-LD-LO") (class "Default")
      (node (ref "IC1") (pin "10") (pinfunction "I1_10") (pintype "input"))
      (node (ref "IC15") (pin "10") (pinfunction "I1_10") (pintype "input"))
      (node (ref "IC25") (pin "10") (pinfunction "I1_10") (pintype "input"))
      (node (ref "IC47") (pin "10") (pinfunction "I1_10") (pintype "input"))
      (node (ref "X1") (pin "B18") (pinfunction "B_B18") (pintype "passive"))
    )
    (net (code "35") (name "-REG-RD-HI") (class "Default")
      (node (ref "IC2") (pin "13") (pinfunction "I1_13") (pintype "input"))
      (node (ref "IC2") (pin "5") (pinfunction "I1_5") (pintype "input"))
      (node (ref "IC26") (pin "13") (pinfunction "I1_13") (pintype "input"))
      (node (ref "IC26") (pin "5") (pinfunction "I1_5") (pintype "input"))
      (node (ref "X1") (pin "B19") (pinfunction "B_B19") (pintype "passive"))
    )
    (net (code "36") (name "-REG-RD-LO") (class "Default")
      (node (ref "IC2") (pin "10") (pinfunction "I1_10") (pintype "input"))
      (node (ref "IC2") (pin "2") (pinfunction "I1_2") (pintype "input"))
      (node (ref "IC26") (pin "10") (pinfunction "I1_10") (pintype "input"))
      (node (ref "IC26") (pin "2") (pinfunction "I1_2") (pintype "input"))
      (node (ref "X1") (pin "B17") (pinfunction "B_B17") (pintype "passive"))
    )
    (net (code "37") (name "-REG-UP") (class "Default")
      (node (ref "IC1") (pin "2") (pinfunction "I1_2") (pintype "input"))
      (node (ref "IC15") (pin "2") (pinfunction "I1_2") (pintype "input"))
      (node (ref "IC25") (pin "2") (pinfunction "I1_2") (pintype "input"))
      (node (ref "IC47") (pin "2") (pinfunction "I1_2") (pintype "input"))
      (node (ref "X1") (pin "B22") (pinfunction "B_B22") (pintype "passive"))
    )
    (net (code "38") (name "-RESET") (class "Default")
      (node (ref "IC34") (pin "2") (pinfunction "I1_2") (pintype "input"))
      (node (ref "X1") (pin "C30") (pinfunction "B_C30") (pintype "passive"))
    )
    (net (code "39") (name "-RLD0") (class "Default")
      (node (ref "IC32") (pin "12") (pinfunction "Y0_12") (pintype "output"))
      (node (ref "J2") (pin "1") (pinfunction "1_1") (pintype "passive"))
    )
    (net (code "40") (name "-RRD0") (class "Default")
      (node (ref "IC32") (pin "4") (pinfunction "Y0_4") (pintype "output"))
      (node (ref "J1") (pin "1") (pinfunction "1_1") (pintype "passive"))
    )
    (net (code "41") (name "-RUN") (class "Default")
      (node (ref "X1") (pin "C29") (pinfunction "B_C29") (pintype "passive"))
    )
    (net (code "42") (name "-SR-LD") (class "Default")
      (node (ref "X1") (pin "C23") (pinfunction "B_C23") (pintype "passive"))
    )
    (net (code "43") (name "-TMP-REG-LD0") (class "Default")
      (node (ref "X1") (pin "B28") (pinfunction "B_B28") (pintype "passive"))
    )
    (net (code "44") (name "-TMP-REG-LD1") (class "Default")
      (node (ref "X1") (pin "B30") (pinfunction "B_B30") (pintype "passive"))
    )
    (net (code "45") (name "-TMP-REG-RD0") (class "Default")
      (node (ref "X1") (pin "B27") (pinfunction "B_B27") (pintype "passive"))
    )
    (net (code "46") (name "-TMP-REG-RD1") (class "Default")
      (node (ref "X1") (pin "B29") (pinfunction "B_B29") (pintype "passive"))
    )
    (net (code "47") (name "-VMA") (class "Default")
      (node (ref "IC40") (pin "2") (pinfunction "I1_2") (pintype "input"))
      (node (ref "X1") (pin "C12") (pinfunction "B_C12") (pintype "passive"))
    )
    (net (code "48") (name "ADATA0") (class "Default")
      (node (ref "IC13") (pin "9") (pinfunction "Y1_9") (pintype "tri_state"))
      (node (ref "IC19") (pin "15") (pinfunction "A_15") (pintype "input"))
      (node (ref "IC23") (pin "9") (pinfunction "Y1_9") (pintype "tri_state"))
      (node (ref "IC29") (pin "15") (pinfunction "A_15") (pintype "input"))
      (node (ref "IC3") (pin "15") (pinfunction "A_15") (pintype "input"))
      (node (ref "IC35") (pin "18") (pinfunction "B1_18") (pintype "bidirectional"))
      (node (ref "IC45") (pin "9") (pinfunction "Y1_9") (pintype "tri_state"))
      (node (ref "IC7") (pin "9") (pinfunction "Y1_9") (pintype "tri_state"))
      (node (ref "IC9") (pin "15") (pinfunction "A_15") (pintype "input"))
      (node (ref "RN1") (pin "2") (pinfunction "1_2") (pintype "passive"))
    )
    (net (code "49") (name "ADATA1") (class "Default")
      (node (ref "IC13") (pin "7") (pinfunction "Y2_7") (pintype "tri_state"))
      (node (ref "IC19") (pin "1") (pinfunction "B_1") (pintype "input"))
      (node (ref "IC23") (pin "7") (pinfunction "Y2_7") (pintype "tri_state"))
      (node (ref "IC29") (pin "1") (pinfunction "B_1") (pintype "input"))
      (node (ref "IC3") (pin "1") (pinfunction "B_1") (pintype "input"))
      (node (ref "IC35") (pin "17") (pinfunction "B2_17") (pintype "bidirectional"))
      (node (ref "IC45") (pin "7") (pinfunction "Y2_7") (pintype "tri_state"))
      (node (ref "IC7") (pin "7") (pinfunction "Y2_7") (pintype "tri_state"))
      (node (ref "IC9") (pin "1") (pinfunction "B_1") (pintype "input"))
      (node (ref "RN1") (pin "3") (pinfunction "1_3") (pintype "passive"))
    )
    (net (code "50") (name "ADATA2") (class "Default")
      (node (ref "IC13") (pin "5") (pinfunction "Y3_5") (pintype "tri_state"))
      (node (ref "IC19") (pin "10") (pinfunction "C_10") (pintype "input"))
      (node (ref "IC23") (pin "5") (pinfunction "Y3_5") (pintype "tri_state"))
      (node (ref "IC29") (pin "10") (pinfunction "C_10") (pintype "input"))
      (node (ref "IC3") (pin "10") (pinfunction "C_10") (pintype "input"))
      (node (ref "IC35") (pin "16") (pinfunction "B3_16") (pintype "bidirectional"))
      (node (ref "IC45") (pin "5") (pinfunction "Y3_5") (pintype "tri_state"))
      (node (ref "IC7") (pin "5") (pinfunction "Y3_5") (pintype "tri_state"))
      (node (ref "IC9") (pin "10") (pinfunction "C_10") (pintype "input"))
      (node (ref "RN1") (pin "4") (pinfunction "1_4") (pintype "passive"))
    )
    (net (code "51") (name "ADATA3") (class "Default")
      (node (ref "IC13") (pin "3") (pinfunction "Y4_3") (pintype "tri_state"))
      (node (ref "IC19") (pin "9") (pinfunction "D_9") (pintype "input"))
      (node (ref "IC23") (pin "3") (pinfunction "Y4_3") (pintype "tri_state"))
      (node (ref "IC29") (pin "9") (pinfunction "D_9") (pintype "input"))
      (node (ref "IC3") (pin "9") (pinfunction "D_9") (pintype "input"))
      (node (ref "IC35") (pin "15") (pinfunction "B4_15") (pintype "bidirectional"))
      (node (ref "IC45") (pin "3") (pinfunction "Y4_3") (pintype "tri_state"))
      (node (ref "IC7") (pin "3") (pinfunction "Y4_3") (pintype "tri_state"))
      (node (ref "IC9") (pin "9") (pinfunction "D_9") (pintype "input"))
      (node (ref "RN1") (pin "5") (pinfunction "1_5") (pintype "passive"))
    )
    (net (code "52") (name "ADATA4") (class "Default")
      (node (ref "IC10") (pin "15") (pinfunction "A_15") (pintype "input"))
      (node (ref "IC13") (pin "18") (pinfunction "Y1_18") (pintype "tri_state"))
      (node (ref "IC20") (pin "15") (pinfunction "A_15") (pintype "input"))
      (node (ref "IC23") (pin "18") (pinfunction "Y1_18") (pintype "tri_state"))
      (node (ref "IC30") (pin "15") (pinfunction "A_15") (pintype "input"))
      (node (ref "IC35") (pin "14") (pinfunction "B5_14") (pintype "bidirectional"))
      (node (ref "IC4") (pin "15") (pinfunction "A_15") (pintype "input"))
      (node (ref "IC45") (pin "18") (pinfunction "Y1_18") (pintype "tri_state"))
      (node (ref "IC7") (pin "18") (pinfunction "Y1_18") (pintype "tri_state"))
      (node (ref "RN1") (pin "6") (pinfunction "1_6") (pintype "passive"))
    )
    (net (code "53") (name "ADATA5") (class "Default")
      (node (ref "IC10") (pin "1") (pinfunction "B_1") (pintype "input"))
      (node (ref "IC13") (pin "16") (pinfunction "Y2_16") (pintype "tri_state"))
      (node (ref "IC20") (pin "1") (pinfunction "B_1") (pintype "input"))
      (node (ref "IC23") (pin "16") (pinfunction "Y2_16") (pintype "tri_state"))
      (node (ref "IC30") (pin "1") (pinfunction "B_1") (pintype "input"))
      (node (ref "IC35") (pin "13") (pinfunction "B6_13") (pintype "bidirectional"))
      (node (ref "IC4") (pin "1") (pinfunction "B_1") (pintype "input"))
      (node (ref "IC45") (pin "16") (pinfunction "Y2_16") (pintype "tri_state"))
      (node (ref "IC7") (pin "16") (pinfunction "Y2_16") (pintype "tri_state"))
      (node (ref "RN1") (pin "7") (pinfunction "1_7") (pintype "passive"))
    )
    (net (code "54") (name "ADATA6") (class "Default")
      (node (ref "IC10") (pin "10") (pinfunction "C_10") (pintype "input"))
      (node (ref "IC13") (pin "14") (pinfunction "Y3_14") (pintype "tri_state"))
      (node (ref "IC20") (pin "10") (pinfunction "C_10") (pintype "input"))
      (node (ref "IC23") (pin "14") (pinfunction "Y3_14") (pintype "tri_state"))
      (node (ref "IC30") (pin "10") (pinfunction "C_10") (pintype "input"))
      (node (ref "IC35") (pin "12") (pinfunction "B7_12") (pintype "bidirectional"))
      (node (ref "IC4") (pin "10") (pinfunction "C_10") (pintype "input"))
      (node (ref "IC45") (pin "14") (pinfunction "Y3_14") (pintype "tri_state"))
      (node (ref "IC7") (pin "14") (pinfunction "Y3_14") (pintype "tri_state"))
      (node (ref "RN1") (pin "8") (pinfunction "1_8") (pintype "passive"))
    )
    (net (code "55") (name "ADATA7") (class "Default")
      (node (ref "IC10") (pin "9") (pinfunction "D_9") (pintype "input"))
      (node (ref "IC13") (pin "12") (pinfunction "Y4_12") (pintype "tri_state"))
      (node (ref "IC20") (pin "9") (pinfunction "D_9") (pintype "input"))
      (node (ref "IC23") (pin "12") (pinfunction "Y4_12") (pintype "tri_state"))
      (node (ref "IC30") (pin "9") (pinfunction "D_9") (pintype "input"))
      (node (ref "IC35") (pin "11") (pinfunction "B8_11") (pintype "bidirectional"))
      (node (ref "IC4") (pin "9") (pinfunction "D_9") (pintype "input"))
      (node (ref "IC45") (pin "12") (pinfunction "Y4_12") (pintype "tri_state"))
      (node (ref "IC7") (pin "12") (pinfunction "Y4_12") (pintype "tri_state"))
      (node (ref "RN1") (pin "9") (pinfunction "1_9") (pintype "passive"))
    )
    (net (code "56") (name "ADATA8") (class "Default")
      (node (ref "IC11") (pin "15") (pinfunction "A_15") (pintype "input"))
      (node (ref "IC14") (pin "9") (pinfunction "Y1_9") (pintype "tri_state"))
      (node (ref "IC21") (pin "15") (pinfunction "A_15") (pintype "input"))
      (node (ref "IC24") (pin "9") (pinfunction "Y1_9") (pintype "tri_state"))
      (node (ref "IC36") (pin "18") (pinfunction "B1_18") (pintype "bidirectional"))
      (node (ref "IC37") (pin "18") (pinfunction "B1_18") (pintype "bidirectional"))
      (node (ref "IC43") (pin "15") (pinfunction "A_15") (pintype "input"))
      (node (ref "IC46") (pin "9") (pinfunction "Y1_9") (pintype "tri_state"))
      (node (ref "IC5") (pin "15") (pinfunction "A_15") (pintype "input"))
      (node (ref "IC8") (pin "9") (pinfunction "Y1_9") (pintype "tri_state"))
      (node (ref "RN2") (pin "2") (pinfunction "1_2") (pintype "passive"))
    )
    (net (code "57") (name "ADATA9") (class "Default")
      (node (ref "IC11") (pin "1") (pinfunction "B_1") (pintype "input"))
      (node (ref "IC14") (pin "7") (pinfunction "Y2_7") (pintype "tri_state"))
      (node (ref "IC21") (pin "1") (pinfunction "B_1") (pintype "input"))
      (node (ref "IC24") (pin "7") (pinfunction "Y2_7") (pintype "tri_state"))
      (node (ref "IC36") (pin "17") (pinfunction "B2_17") (pintype "bidirectional"))
      (node (ref "IC37") (pin "17") (pinfunction "B2_17") (pintype "bidirectional"))
      (node (ref "IC43") (pin "1") (pinfunction "B_1") (pintype "input"))
      (node (ref "IC46") (pin "7") (pinfunction "Y2_7") (pintype "tri_state"))
      (node (ref "IC5") (pin "1") (pinfunction "B_1") (pintype "input"))
      (node (ref "IC8") (pin "7") (pinfunction "Y2_7") (pintype "tri_state"))
      (node (ref "RN2") (pin "3") (pinfunction "1_3") (pintype "passive"))
    )
    (net (code "58") (name "ADATA10") (class "Default")
      (node (ref "IC11") (pin "10") (pinfunction "C_10") (pintype "input"))
      (node (ref "IC14") (pin "5") (pinfunction "Y3_5") (pintype "tri_state"))
      (node (ref "IC21") (pin "10") (pinfunction "C_10") (pintype "input"))
      (node (ref "IC24") (pin "5") (pinfunction "Y3_5") (pintype "tri_state"))
      (node (ref "IC36") (pin "16") (pinfunction "B3_16") (pintype "bidirectional"))
      (node (ref "IC37") (pin "16") (pinfunction "B3_16") (pintype "bidirectional"))
      (node (ref "IC43") (pin "10") (pinfunction "C_10") (pintype "input"))
      (node (ref "IC46") (pin "5") (pinfunction "Y3_5") (pintype "tri_state"))
      (node (ref "IC5") (pin "10") (pinfunction "C_10") (pintype "input"))
      (node (ref "IC8") (pin "5") (pinfunction "Y3_5") (pintype "tri_state"))
      (node (ref "RN2") (pin "4") (pinfunction "1_4") (pintype "passive"))
    )
    (net (code "59") (name "ADATA11") (class "Default")
      (node (ref "IC11") (pin "9") (pinfunction "D_9") (pintype "input"))
      (node (ref "IC14") (pin "3") (pinfunction "Y4_3") (pintype "tri_state"))
      (node (ref "IC21") (pin "9") (pinfunction "D_9") (pintype "input"))
      (node (ref "IC24") (pin "3") (pinfunction "Y4_3") (pintype "tri_state"))
      (node (ref "IC36") (pin "15") (pinfunction "B4_15") (pintype "bidirectional"))
      (node (ref "IC37") (pin "15") (pinfunction "B4_15") (pintype "bidirectional"))
      (node (ref "IC43") (pin "9") (pinfunction "D_9") (pintype "input"))
      (node (ref "IC46") (pin "3") (pinfunction "Y4_3") (pintype "tri_state"))
      (node (ref "IC5") (pin "9") (pinfunction "D_9") (pintype "input"))
      (node (ref "IC8") (pin "3") (pinfunction "Y4_3") (pintype "tri_state"))
      (node (ref "RN2") (pin "5") (pinfunction "1_5") (pintype "passive"))
    )
    (net (code "60") (name "ADATA12") (class "Default")
      (node (ref "IC12") (pin "15") (pinfunction "A_15") (pintype "input"))
      (node (ref "IC14") (pin "18") (pinfunction "Y1_18") (pintype "tri_state"))
      (node (ref "IC22") (pin "15") (pinfunction "A_15") (pintype "input"))
      (node (ref "IC24") (pin "18") (pinfunction "Y1_18") (pintype "tri_state"))
      (node (ref "IC36") (pin "14") (pinfunction "B5_14") (pintype "bidirectional"))
      (node (ref "IC37") (pin "14") (pinfunction "B5_14") (pintype "bidirectional"))
      (node (ref "IC44") (pin "15") (pinfunction "A_15") (pintype "input"))
      (node (ref "IC46") (pin "18") (pinfunction "Y1_18") (pintype "tri_state"))
      (node (ref "IC6") (pin "15") (pinfunction "A_15") (pintype "input"))
      (node (ref "IC8") (pin "18") (pinfunction "Y1_18") (pintype "tri_state"))
      (node (ref "RN2") (pin "6") (pinfunction "1_6") (pintype "passive"))
    )
    (net (code "61") (name "ADATA13") (class "Default")
      (node (ref "IC12") (pin "1") (pinfunction "B_1") (pintype "input"))
      (node (ref "IC14") (pin "16") (pinfunction "Y2_16") (pintype "tri_state"))
      (node (ref "IC22") (pin "1") (pinfunction "B_1") (pintype "input"))
      (node (ref "IC24") (pin "16") (pinfunction "Y2_16") (pintype "tri_state"))
      (node (ref "IC36") (pin "13") (pinfunction "B6_13") (pintype "bidirectional"))
      (node (ref "IC37") (pin "13") (pinfunction "B6_13") (pintype "bidirectional"))
      (node (ref "IC44") (pin "1") (pinfunction "B_1") (pintype "input"))
      (node (ref "IC46") (pin "16") (pinfunction "Y2_16") (pintype "tri_state"))
      (node (ref "IC6") (pin "1") (pinfunction "B_1") (pintype "input"))
      (node (ref "IC8") (pin "16") (pinfunction "Y2_16") (pintype "tri_state"))
      (node (ref "RN2") (pin "7") (pinfunction "1_7") (pintype "passive"))
    )
    (net (code "62") (name "ADATA14") (class "Default")
      (node (ref "IC12") (pin "10") (pinfunction "C_10") (pintype "input"))
      (node (ref "IC14") (pin "14") (pinfunction "Y3_14") (pintype "tri_state"))
      (node (ref "IC22") (pin "10") (pinfunction "C_10") (pintype "input"))
      (node (ref "IC24") (pin "14") (pinfunction "Y3_14") (pintype "tri_state"))
      (node (ref "IC36") (pin "12") (pinfunction "B7_12") (pintype "bidirectional"))
      (node (ref "IC37") (pin "12") (pinfunction "B7_12") (pintype "bidirectional"))
      (node (ref "IC44") (pin "10") (pinfunction "C_10") (pintype "input"))
      (node (ref "IC46") (pin "14") (pinfunction "Y3_14") (pintype "tri_state"))
      (node (ref "IC6") (pin "10") (pinfunction "C_10") (pintype "input"))
      (node (ref "IC8") (pin "14") (pinfunction "Y3_14") (pintype "tri_state"))
      (node (ref "RN2") (pin "8") (pinfunction "1_8") (pintype "passive"))
    )
    (net (code "63") (name "ADATA15") (class "Default")
      (node (ref "IC12") (pin "9") (pinfunction "D_9") (pintype "input"))
      (node (ref "IC14") (pin "12") (pinfunction "Y4_12") (pintype "tri_state"))
      (node (ref "IC22") (pin "9") (pinfunction "D_9") (pintype "input"))
      (node (ref "IC24") (pin "12") (pinfunction "Y4_12") (pintype "tri_state"))
      (node (ref "IC36") (pin "11") (pinfunction "B8_11") (pintype "bidirectional"))
      (node (ref "IC37") (pin "11") (pinfunction "B8_11") (pintype "bidirectional"))
      (node (ref "IC44") (pin "9") (pinfunction "D_9") (pintype "input"))
      (node (ref "IC46") (pin "12") (pinfunction "Y4_12") (pintype "tri_state"))
      (node (ref "IC6") (pin "9") (pinfunction "D_9") (pintype "input"))
      (node (ref "IC8") (pin "12") (pinfunction "Y4_12") (pintype "tri_state"))
      (node (ref "RN2") (pin "9") (pinfunction "1_9") (pintype "passive"))
    )
    (net (code "64") (name "ADDR-REG-ID0") (class "Default")
      (node (ref "IC38") (pin "2") (pinfunction "A_2") (pintype "input"))
      (node (ref "X1") (pin "C3") (pinfunction "B_C3") (pintype "passive"))
    )
    (net (code "65") (name "ADDR-REG-ID1") (class "Default")
      (node (ref "IC38") (pin "3") (pinfunction "B_3") (pintype "input"))
      (node (ref "X1") (pin "C4") (pinfunction "B_C4") (pintype "passive"))
    )
    (net (code "66") (name "ADDR-REG-ID2") (class "Default")
      (node (ref "IC38") (pin "14") (pinfunction "A_14") (pintype "input"))
      (node (ref "X1") (pin "C5") (pinfunction "B_C5") (pintype "passive"))
    )
    (net (code "67") (name "ADDR-REG-ID3") (class "Default")
      (node (ref "IC38") (pin "13") (pinfunction "B_13") (pintype "input"))
      (node (ref "X1") (pin "C6") (pinfunction "B_C6") (pintype "passive"))
    )
    (net (code "68") (name "ADDR0") (class "Default")
      (node (ref "IC17") (pin "18") (pinfunction "Y1_18") (pintype "tri_state"))
      (node (ref "IC27") (pin "18") (pinfunction "Y1_18") (pintype "tri_state"))
      (node (ref "IC41") (pin "18") (pinfunction "Y1_18") (pintype "tri_state"))
      (node (ref "IC49") (pin "18") (pinfunction "Y1_18") (pintype "tri_state"))
      (node (ref "X1") (pin "A3") (pinfunction "B_A3") (pintype "passive"))
    )
    (net (code "69") (name "ADDR1") (class "Default")
      (node (ref "IC17") (pin "16") (pinfunction "Y2_16") (pintype "tri_state"))
      (node (ref "IC27") (pin "16") (pinfunction "Y2_16") (pintype "tri_state"))
      (node (ref "IC41") (pin "16") (pinfunction "Y2_16") (pintype "tri_state"))
      (node (ref "IC49") (pin "16") (pinfunction "Y2_16") (pintype "tri_state"))
      (node (ref "X1") (pin "A4") (pinfunction "B_A4") (pintype "passive"))
    )
    (net (code "70") (name "ADDR2") (class "Default")
      (node (ref "IC17") (pin "14") (pinfunction "Y3_14") (pintype "tri_state"))
      (node (ref "IC27") (pin "14") (pinfunction "Y3_14") (pintype "tri_state"))
      (node (ref "IC41") (pin "14") (pinfunction "Y3_14") (pintype "tri_state"))
      (node (ref "IC49") (pin "14") (pinfunction "Y3_14") (pintype "tri_state"))
      (node (ref "X1") (pin "A5") (pinfunction "B_A5") (pintype "passive"))
    )
    (net (code "71") (name "ADDR3") (class "Default")
      (node (ref "IC17") (pin "12") (pinfunction "Y4_12") (pintype "tri_state"))
      (node (ref "IC27") (pin "12") (pinfunction "Y4_12") (pintype "tri_state"))
      (node (ref "IC41") (pin "12") (pinfunction "Y4_12") (pintype "tri_state"))
      (node (ref "IC49") (pin "12") (pinfunction "Y4_12") (pintype "tri_state"))
      (node (ref "X1") (pin "A6") (pinfunction "B_A6") (pintype "passive"))
    )
    (net (code "72") (name "ADDR4") (class "Default")
      (node (ref "IC17") (pin "9") (pinfunction "Y1_9") (pintype "tri_state"))
      (node (ref "IC27") (pin "9") (pinfunction "Y1_9") (pintype "tri_state"))
      (node (ref "IC41") (pin "9") (pinfunction "Y1_9") (pintype "tri_state"))
      (node (ref "IC49") (pin "9") (pinfunction "Y1_9") (pintype "tri_state"))
      (node (ref "X1") (pin "A7") (pinfunction "B_A7") (pintype "passive"))
    )
    (net (code "73") (name "ADDR5") (class "Default")
      (node (ref "IC17") (pin "7") (pinfunction "Y2_7") (pintype "tri_state"))
      (node (ref "IC27") (pin "7") (pinfunction "Y2_7") (pintype "tri_state"))
      (node (ref "IC41") (pin "7") (pinfunction "Y2_7") (pintype "tri_state"))
      (node (ref "IC49") (pin "7") (pinfunction "Y2_7") (pintype "tri_state"))
      (node (ref "X1") (pin "A8") (pinfunction "B_A8") (pintype "passive"))
    )
    (net (code "74") (name "ADDR6") (class "Default")
      (node (ref "IC17") (pin "5") (pinfunction "Y3_5") (pintype "tri_state"))
      (node (ref "IC27") (pin "5") (pinfunction "Y3_5") (pintype "tri_state"))
      (node (ref "IC41") (pin "5") (pinfunction "Y3_5") (pintype "tri_state"))
      (node (ref "IC49") (pin "5") (pinfunction "Y3_5") (pintype "tri_state"))
      (node (ref "X1") (pin "A9") (pinfunction "B_A9") (pintype "passive"))
    )
    (net (code "75") (name "ADDR7") (class "Default")
      (node (ref "IC17") (pin "3") (pinfunction "Y4_3") (pintype "tri_state"))
      (node (ref "IC27") (pin "3") (pinfunction "Y4_3") (pintype "tri_state"))
      (node (ref "IC41") (pin "3") (pinfunction "Y4_3") (pintype "tri_state"))
      (node (ref "IC49") (pin "3") (pinfunction "Y4_3") (pintype "tri_state"))
      (node (ref "X1") (pin "A10") (pinfunction "B_A10") (pintype "passive"))
    )
    (net (code "76") (name "ADDR8") (class "Default")
      (node (ref "IC18") (pin "18") (pinfunction "Y1_18") (pintype "tri_state"))
      (node (ref "IC28") (pin "18") (pinfunction "Y1_18") (pintype "tri_state"))
      (node (ref "IC42") (pin "18") (pinfunction "Y1_18") (pintype "tri_state"))
      (node (ref "IC50") (pin "18") (pinfunction "Y1_18") (pintype "tri_state"))
      (node (ref "X1") (pin "A11") (pinfunction "B_A11") (pintype "passive"))
    )
    (net (code "77") (name "ADDR9") (class "Default")
      (node (ref "IC18") (pin "16") (pinfunction "Y2_16") (pintype "tri_state"))
      (node (ref "IC28") (pin "16") (pinfunction "Y2_16") (pintype "tri_state"))
      (node (ref "IC42") (pin "16") (pinfunction "Y2_16") (pintype "tri_state"))
      (node (ref "IC50") (pin "16") (pinfunction "Y2_16") (pintype "tri_state"))
      (node (ref "X1") (pin "A12") (pinfunction "B_A12") (pintype "passive"))
    )
    (net (code "78") (name "ADDR10") (class "Default")
      (node (ref "IC18") (pin "14") (pinfunction "Y3_14") (pintype "tri_state"))
      (node (ref "IC28") (pin "14") (pinfunction "Y3_14") (pintype "tri_state"))
      (node (ref "IC42") (pin "14") (pinfunction "Y3_14") (pintype "tri_state"))
      (node (ref "IC50") (pin "14") (pinfunction "Y3_14") (pintype "tri_state"))
      (node (ref "X1") (pin "A13") (pinfunction "B_A13") (pintype "passive"))
    )
    (net (code "79") (name "ADDR11") (class "Default")
      (node (ref "IC18") (pin "12") (pinfunction "Y4_12") (pintype "tri_state"))
      (node (ref "IC28") (pin "12") (pinfunction "Y4_12") (pintype "tri_state"))
      (node (ref "IC42") (pin "12") (pinfunction "Y4_12") (pintype "tri_state"))
      (node (ref "IC50") (pin "12") (pinfunction "Y4_12") (pintype "tri_state"))
      (node (ref "X1") (pin "A14") (pinfunction "B_A14") (pintype "passive"))
    )
    (net (code "80") (name "ADDR12") (class "Default")
      (node (ref "IC18") (pin "9") (pinfunction "Y1_9") (pintype "tri_state"))
      (node (ref "IC28") (pin "9") (pinfunction "Y1_9") (pintype "tri_state"))
      (node (ref "IC42") (pin "9") (pinfunction "Y1_9") (pintype "tri_state"))
      (node (ref "IC50") (pin "9") (pinfunction "Y1_9") (pintype "tri_state"))
      (node (ref "X1") (pin "A15") (pinfunction "B_A15") (pintype "passive"))
    )
    (net (code "81") (name "ADDR13") (class "Default")
      (node (ref "IC18") (pin "7") (pinfunction "Y2_7") (pintype "tri_state"))
      (node (ref "IC28") (pin "7") (pinfunction "Y2_7") (pintype "tri_state"))
      (node (ref "IC42") (pin "7") (pinfunction "Y2_7") (pintype "tri_state"))
      (node (ref "IC50") (pin "7") (pinfunction "Y2_7") (pintype "tri_state"))
      (node (ref "X1") (pin "A16") (pinfunction "B_A16") (pintype "passive"))
    )
    (net (code "82") (name "ADDR14") (class "Default")
      (node (ref "IC18") (pin "5") (pinfunction "Y3_5") (pintype "tri_state"))
      (node (ref "IC28") (pin "5") (pinfunction "Y3_5") (pintype "tri_state"))
      (node (ref "IC42") (pin "5") (pinfunction "Y3_5") (pintype "tri_state"))
      (node (ref "IC50") (pin "5") (pinfunction "Y3_5") (pintype "tri_state"))
      (node (ref "X1") (pin "A17") (pinfunction "B_A17") (pintype "passive"))
    )
    (net (code "83") (name "ADDR15") (class "Default")
      (node (ref "IC18") (pin "3") (pinfunction "Y4_3") (pintype "tri_state"))
      (node (ref "IC28") (pin "3") (pinfunction "Y4_3") (pintype "tri_state"))
      (node (ref "IC42") (pin "3") (pinfunction "Y4_3") (pintype "tri_state"))
      (node (ref "IC50") (pin "3") (pinfunction "Y4_3") (pintype "tri_state"))
      (node (ref "X1") (pin "A18") (pinfunction "B_A18") (pintype "passive"))
    )
    (net (code "84") (name "ALU0") (class "Default")
      (node (ref "X1") (pin "C16") (pinfunction "B_C16") (pintype "passive"))
    )
    (net (code "85") (name "ALU1") (class "Default")
      (node (ref "X1") (pin "C17") (pinfunction "B_C17") (pintype "passive"))
    )
    (net (code "86") (name "ALU2") (class "Default")
      (node (ref "X1") (pin "C18") (pinfunction "B_C18") (pintype "passive"))
    )
    (net (code "87") (name "ALU3") (class "Default")
      (node (ref "X1") (pin "C19") (pinfunction "B_C19") (pintype "passive"))
    )
    (net (code "88") (name "BR-COND") (class "Default")
      (node (ref "X1") (pin "C24") (pinfunction "B_C24") (pintype "passive"))
    )
    (net (code "89") (name "BUS-DIR") (class "Default")
      (node (ref "IC34") (pin "4") (pinfunction "O_4") (pintype "output"))
      (node (ref "IC35") (pin "1") (pinfunction "DIR_1") (pintype "input"))
      (node (ref "IC36") (pin "1") (pinfunction "DIR_1") (pintype "input"))
      (node (ref "IC37") (pin "1") (pinfunction "DIR_1") (pintype "input"))
    )
    (net (code "90") (name "DATA0") (class "Default")
      (node (ref "IC35") (pin "2") (pinfunction "A1_2") (pintype "bidirectional"))
      (node (ref "IC37") (pin "2") (pinfunction "A1_2") (pintype "bidirectional"))
      (node (ref "X1") (pin "A19") (pinfunction "B_A19") (pintype "passive"))
    )
    (net (code "91") (name "DATA1") (class "Default")
      (node (ref "IC35") (pin "3") (pinfunction "A2_3") (pintype "bidirectional"))
      (node (ref "IC37") (pin "3") (pinfunction "A2_3") (pintype "bidirectional"))
      (node (ref "X1") (pin "A20") (pinfunction "B_A20") (pintype "passive"))
    )
    (net (code "92") (name "DATA2") (class "Default")
      (node (ref "IC35") (pin "4") (pinfunction "A3_4") (pintype "bidirectional"))
      (node (ref "IC37") (pin "4") (pinfunction "A3_4") (pintype "bidirectional"))
      (node (ref "X1") (pin "A21") (pinfunction "B_A21") (pintype "passive"))
    )
    (net (code "93") (name "DATA3") (class "Default")
      (node (ref "IC35") (pin "5") (pinfunction "A4_5") (pintype "bidirectional"))
      (node (ref "IC37") (pin "5") (pinfunction "A4_5") (pintype "bidirectional"))
      (node (ref "X1") (pin "A22") (pinfunction "B_A22") (pintype "passive"))
    )
    (net (code "94") (name "DATA4") (class "Default")
      (node (ref "IC35") (pin "6") (pinfunction "A5_6") (pintype "bidirectional"))
      (node (ref "IC37") (pin "6") (pinfunction "A5_6") (pintype "bidirectional"))
      (node (ref "X1") (pin "A23") (pinfunction "B_A23") (pintype "passive"))
    )
    (net (code "95") (name "DATA5") (class "Default")
      (node (ref "IC35") (pin "7") (pinfunction "A6_7") (pintype "bidirectional"))
      (node (ref "IC37") (pin "7") (pinfunction "A6_7") (pintype "bidirectional"))
      (node (ref "X1") (pin "A24") (pinfunction "B_A24") (pintype "passive"))
    )
    (net (code "96") (name "DATA6") (class "Default")
      (node (ref "IC35") (pin "8") (pinfunction "A7_8") (pintype "bidirectional"))
      (node (ref "IC37") (pin "8") (pinfunction "A7_8") (pintype "bidirectional"))
      (node (ref "X1") (pin "A25") (pinfunction "B_A25") (pintype "passive"))
    )
    (net (code "97") (name "DATA7") (class "Default")
      (node (ref "IC35") (pin "9") (pinfunction "A8_9") (pintype "bidirectional"))
      (node (ref "IC37") (pin "9") (pinfunction "A8_9") (pintype "bidirectional"))
      (node (ref "X1") (pin "A26") (pinfunction "B_A26") (pintype "passive"))
    )
    (net (code "98") (name "DATA8") (class "Default")
      (node (ref "IC36") (pin "2") (pinfunction "A1_2") (pintype "bidirectional"))
      (node (ref "X1") (pin "A27") (pinfunction "B_A27") (pintype "passive"))
    )
    (net (code "99") (name "DATA9") (class "Default")
      (node (ref "IC36") (pin "3") (pinfunction "A2_3") (pintype "bidirectional"))
      (node (ref "X1") (pin "A28") (pinfunction "B_A28") (pintype "passive"))
    )
    (net (code "100") (name "DATA10") (class "Default")
      (node (ref "IC36") (pin "4") (pinfunction "A3_4") (pintype "bidirectional"))
      (node (ref "X1") (pin "A29") (pinfunction "B_A29") (pintype "passive"))
    )
    (net (code "101") (name "DATA11") (class "Default")
      (node (ref "IC36") (pin "5") (pinfunction "A4_5") (pintype "bidirectional"))
      (node (ref "X1") (pin "A30") (pinfunction "B_A30") (pintype "passive"))
    )
    (net (code "102") (name "DATA12") (class "Default")
      (node (ref "IC36") (pin "6") (pinfunction "A5_6") (pintype "bidirectional"))
      (node (ref "X1") (pin "B3") (pinfunction "B_B3") (pintype "passive"))
    )
    (net (code "103") (name "DATA13") (class "Default")
      (node (ref "IC36") (pin "7") (pinfunction "A6_7") (pintype "bidirectional"))
      (node (ref "X1") (pin "B4") (pinfunction "B_B4") (pintype "passive"))
    )
    (net (code "104") (name "DATA14") (class "Default")
      (node (ref "IC36") (pin "8") (pinfunction "A7_8") (pintype "bidirectional"))
      (node (ref "X1") (pin "B5") (pinfunction "B_B5") (pintype "passive"))
    )
    (net (code "105") (name "DATA15") (class "Default")
      (node (ref "IC36") (pin "9") (pinfunction "A8_9") (pintype "bidirectional"))
      (node (ref "X1") (pin "B6") (pinfunction "B_B6") (pintype "passive"))
    )
    (net (code "106") (name "GND") (class "Default")
      (node (ref "C1") (pin "2") (pinfunction "2_2") (pintype "passive"))
      (node (ref "C10") (pin "2") (pinfunction "2_2") (pintype "passive"))
      (node (ref "C11") (pin "2") (pinfunction "2_2") (pintype "passive"))
      (node (ref "C12") (pin "2") (pinfunction "2_2") (pintype "passive"))
      (node (ref "C13") (pin "2") (pinfunction "2_2") (pintype "passive"))
      (node (ref "C14") (pin "2") (pinfunction "2_2") (pintype "passive"))
      (node (ref "C15") (pin "2") (pinfunction "2_2") (pintype "passive"))
      (node (ref "C16") (pin "2") (pinfunction "2_2") (pintype "passive"))
      (node (ref "C17") (pin "2") (pinfunction "2_2") (pintype "passive"))
      (node (ref "C18") (pin "2") (pinfunction "2_2") (pintype "passive"))
      (node (ref "C19") (pin "2") (pinfunction "2_2") (pintype "passive"))
      (node (ref "C2") (pin "2") (pinfunction "2_2") (pintype "passive"))
      (node (ref "C20") (pin "2") (pinfunction "2_2") (pintype "passive"))
      (node (ref "C21") (pin "2") (pinfunction "2_2") (pintype "passive"))
      (node (ref "C22") (pin "2") (pinfunction "2_2") (pintype "passive"))
      (node (ref "C23") (pin "2") (pinfunction "2_2") (pintype "passive"))
      (node (ref "C24") (pin "2") (pinfunction "2_2") (pintype "passive"))
      (node (ref "C25") (pin "2") (pinfunction "2_2") (pintype "passive"))
      (node (ref "C26") (pin "2") (pinfunction "2_2") (pintype "passive"))
      (node (ref "C27") (pin "2") (pinfunction "2_2") (pintype "passive"))
      (node (ref "C28") (pin "2") (pinfunction "2_2") (pintype "passive"))
      (node (ref "C29") (pin "2") (pinfunction "2_2") (pintype "passive"))
      (node (ref "C3") (pin "2") (pinfunction "2_2") (pintype "passive"))
      (node (ref "C30") (pin "2") (pinfunction "2_2") (pintype "passive"))
      (node (ref "C31") (pin "2") (pinfunction "2_2") (pintype "passive"))
      (node (ref "C32") (pin "2") (pinfunction "2_2") (pintype "passive"))
      (node (ref "C33") (pin "2") (pinfunction "2_2") (pintype "passive"))
      (node (ref "C34") (pin "2") (pinfunction "2_2") (pintype "passive"))
      (node (ref "C35") (pin "2") (pinfunction "2_2") (pintype "passive"))
      (node (ref "C36") (pin "2") (pinfunction "2_2") (pintype "passive"))
      (node (ref "C37") (pin "2") (pinfunction "2_2") (pintype "passive"))
      (node (ref "C38") (pin "2") (pinfunction "2_2") (pintype "passive"))
      (node (ref "C4") (pin "2") (pinfunction "2_2") (pintype "passive"))
      (node (ref "C5") (pin "2") (pinfunction "2_2") (pintype "passive"))
      (node (ref "C6") (pin "2") (pinfunction "2_2") (pintype "passive"))
      (node (ref "C8") (pin "2") (pinfunction "2_2") (pintype "passive"))
      (node (ref "C9") (pin "2") (pinfunction "2_2") (pintype "passive"))
      (node (ref "IC34") (pin "1") (pinfunction "I0_1") (pintype "input"))
      (node (ref "IC34") (pin "5") (pinfunction "I0_5") (pintype "input"))
      (node (ref "IC34") (pin "8") (pinfunction "I0_8") (pintype "input"))
      (node (ref "PWR") (pin "K") (pinfunction "C_K") (pintype "passive"))
      (node (ref "X1") (pin "A1") (pinfunction "B_A1") (pintype "passive"))
      (node (ref "X1") (pin "A32") (pinfunction "B_A32") (pintype "passive"))
      (node (ref "X1") (pin "B1") (pinfunction "B_B1") (pintype "passive"))
      (node (ref "X1") (pin "B32") (pinfunction "B_B32") (pintype "passive"))
      (node (ref "X1") (pin "C1") (pinfunction "B_C1") (pintype "passive"))
      (node (ref "X1") (pin "C32") (pinfunction "B_C32") (pintype "passive"))
    )
    (net (code "107") (name "IN") (class "Default")
      (node (ref "X1") (pin "C26") (pinfunction "B_C26") (pintype "passive"))
    )
    (net (code "108") (name "IOADDR0") (class "Default")
      (node (ref "X1") (pin "C7") (pinfunction "B_C7") (pintype "passive"))
    )
    (net (code "109") (name "IOADDR1") (class "Default")
      (node (ref "X1") (pin "C8") (pinfunction "B_C8") (pintype "passive"))
    )
    (net (code "110") (name "IOADDR2") (class "Default")
      (node (ref "X1") (pin "C9") (pinfunction "B_C9") (pintype "passive"))
    )
    (net (code "111") (name "IOADDR3") (class "Default")
      (node (ref "X1") (pin "C10") (pinfunction "B_C10") (pintype "passive"))
    )
    (net (code "112") (name "Net-(IC1A-O)") (class "Default")
      (node (ref "IC1") (pin "3") (pinfunction "O_3") (pintype "output"))
      (node (ref "IC3") (pin "5") (pinfunction "UP_5") (pintype "input"))
    )
    (net (code "113") (name "Net-(IC1B-O)") (class "Default")
      (node (ref "IC1") (pin "6") (pinfunction "O_6") (pintype "output"))
      (node (ref "IC3") (pin "4") (pinfunction "DN_4") (pintype "input"))
    )
    (net (code "114") (name "Net-(IC1C-O)") (class "Default")
      (node (ref "IC1") (pin "8") (pinfunction "O_8") (pintype "output"))
      (node (ref "IC3") (pin "11") (pinfunction "LD_11") (pintype "input"))
      (node (ref "IC4") (pin "11") (pinfunction "LD_11") (pintype "input"))
    )
    (net (code "115") (name "Net-(IC1D-O)") (class "Default")
      (node (ref "IC1") (pin "11") (pinfunction "O_11") (pintype "output"))
      (node (ref "IC5") (pin "11") (pinfunction "LD_11") (pintype "input"))
      (node (ref "IC6") (pin "11") (pinfunction "LD_11") (pintype "input"))
    )
    (net (code "116") (name "Net-(IC2A-O)") (class "Default")
      (node (ref "IC2") (pin "3") (pinfunction "O_3") (pintype "output"))
      (node (ref "IC7") (pin "1") (pinfunction "G_1") (pintype "input"))
      (node (ref "IC7") (pin "19") (pinfunction "G_19") (pintype "input"))
    )
    (net (code "117") (name "Net-(IC2B-O)") (class "Default")
      (node (ref "IC2") (pin "6") (pinfunction "O_6") (pintype "output"))
      (node (ref "IC8") (pin "1") (pinfunction "G_1") (pintype "input"))
      (node (ref "IC8") (pin "19") (pinfunction "G_19") (pintype "input"))
    )
    (net (code "118") (name "Net-(IC3A-BO)") (class "Default")
      (node (ref "IC3") (pin "13") (pinfunction "BO_13") (pintype "output"))
      (node (ref "IC4") (pin "4") (pinfunction "DN_4") (pintype "input"))
    )
    (net (code "119") (name "Net-(IC3A-CO)") (class "Default")
      (node (ref "IC3") (pin "12") (pinfunction "CO_12") (pintype "output"))
      (node (ref "IC4") (pin "5") (pinfunction "UP_5") (pintype "input"))
    )
    (net (code "120") (name "Net-(IC3A-QA)") (class "Default")
      (node (ref "IC3") (pin "3") (pinfunction "QA_3") (pintype "output"))
      (node (ref "IC41") (pin "2") (pinfunction "A1_2") (pintype "input"))
      (node (ref "IC7") (pin "11") (pinfunction "A1_11") (pintype "input"))
    )
    (net (code "121") (name "Net-(IC3A-QB)") (class "Default")
      (node (ref "IC3") (pin "2") (pinfunction "QB_2") (pintype "output"))
      (node (ref "IC41") (pin "4") (pinfunction "A2_4") (pintype "input"))
      (node (ref "IC7") (pin "13") (pinfunction "A2_13") (pintype "input"))
    )
    (net (code "122") (name "Net-(IC3A-QC)") (class "Default")
      (node (ref "IC3") (pin "6") (pinfunction "QC_6") (pintype "output"))
      (node (ref "IC41") (pin "6") (pinfunction "A3_6") (pintype "input"))
      (node (ref "IC7") (pin "15") (pinfunction "A3_15") (pintype "input"))
    )
    (net (code "123") (name "Net-(IC3A-QD)") (class "Default")
      (node (ref "IC3") (pin "7") (pinfunction "QD_7") (pintype "output"))
      (node (ref "IC41") (pin "8") (pinfunction "A4_8") (pintype "input"))
      (node (ref "IC7") (pin "17") (pinfunction "A4_17") (pintype "input"))
    )
    (net (code "124") (name "Net-(IC4A-BO)") (class "Default")
      (node (ref "IC4") (pin "13") (pinfunction "BO_13") (pintype "output"))
      (node (ref "IC5") (pin "4") (pinfunction "DN_4") (pintype "input"))
    )
    (net (code "125") (name "Net-(IC4A-CO)") (class "Default")
      (node (ref "IC4") (pin "12") (pinfunction "CO_12") (pintype "output"))
      (node (ref "IC5") (pin "5") (pinfunction "UP_5") (pintype "input"))
    )
    (net (code "126") (name "Net-(IC5A-BO)") (class "Default")
      (node (ref "IC5") (pin "13") (pinfunction "BO_13") (pintype "output"))
      (node (ref "IC6") (pin "4") (pinfunction "DN_4") (pintype "input"))
    )
    (net (code "127") (name "Net-(IC5A-CO)") (class "Default")
      (node (ref "IC5") (pin "12") (pinfunction "CO_12") (pintype "output"))
      (node (ref "IC6") (pin "5") (pinfunction "UP_5") (pintype "input"))
    )
    (net (code "128") (name "Net-(IC10A-BO)") (class "Default")
      (node (ref "IC10") (pin "13") (pinfunction "BO_13") (pintype "output"))
      (node (ref "IC11") (pin "4") (pinfunction "DN_4") (pintype "input"))
    )
    (net (code "129") (name "Net-(IC10A-CO)") (class "Default")
      (node (ref "IC10") (pin "12") (pinfunction "CO_12") (pintype "output"))
      (node (ref "IC11") (pin "5") (pinfunction "UP_5") (pintype "input"))
    )
    (net (code "130") (name "Net-(IC10A-DN)") (class "Default")
      (node (ref "IC10") (pin "4") (pinfunction "DN_4") (pintype "input"))
      (node (ref "IC9") (pin "13") (pinfunction "BO_13") (pintype "output"))
    )
    (net (code "131") (name "Net-(IC10A-LD)") (class "Default")
      (node (ref "IC10") (pin "11") (pinfunction "LD_11") (pintype "input"))
      (node (ref "IC15") (pin "8") (pinfunction "O_8") (pintype "output"))
      (node (ref "IC9") (pin "11") (pinfunction "LD_11") (pintype "input"))
    )
    (net (code "132") (name "Net-(IC10A-QA)") (class "Default")
      (node (ref "IC10") (pin "3") (pinfunction "QA_3") (pintype "output"))
      (node (ref "IC13") (pin "2") (pinfunction "A1_2") (pintype "input"))
      (node (ref "IC17") (pin "11") (pinfunction "A1_11") (pintype "input"))
    )
    (net (code "133") (name "Net-(IC10A-QB)") (class "Default")
      (node (ref "IC10") (pin "2") (pinfunction "QB_2") (pintype "output"))
      (node (ref "IC13") (pin "4") (pinfunction "A2_4") (pintype "input"))
      (node (ref "IC17") (pin "13") (pinfunction "A2_13") (pintype "input"))
    )
    (net (code "134") (name "Net-(IC10A-QC)") (class "Default")
      (node (ref "IC10") (pin "6") (pinfunction "QC_6") (pintype "output"))
      (node (ref "IC13") (pin "6") (pinfunction "A3_6") (pintype "input"))
      (node (ref "IC17") (pin "15") (pinfunction "A3_15") (pintype "input"))
    )
    (net (code "135") (name "Net-(IC10A-QD)") (class "Default")
      (node (ref "IC10") (pin "7") (pinfunction "QD_7") (pintype "output"))
      (node (ref "IC13") (pin "8") (pinfunction "A4_8") (pintype "input"))
      (node (ref "IC17") (pin "17") (pinfunction "A4_17") (pintype "input"))
    )
    (net (code "136") (name "Net-(IC10A-UP)") (class "Default")
      (node (ref "IC10") (pin "5") (pinfunction "UP_5") (pintype "input"))
      (node (ref "IC9") (pin "12") (pinfunction "CO_12") (pintype "output"))
    )
    (net (code "137") (name "Net-(IC11A-BO)") (class "Default")
      (node (ref "IC11") (pin "13") (pinfunction "BO_13") (pintype "output"))
      (node (ref "IC12") (pin "4") (pinfunction "DN_4") (pintype "input"))
    )
    (net (code "138") (name "Net-(IC11A-CO)") (class "Default")
      (node (ref "IC11") (pin "12") (pinfunction "CO_12") (pintype "output"))
      (node (ref "IC12") (pin "5") (pinfunction "UP_5") (pintype "input"))
    )
    (net (code "139") (name "Net-(IC11A-LD)") (class "Default")
      (node (ref "IC11") (pin "11") (pinfunction "LD_11") (pintype "input"))
      (node (ref "IC12") (pin "11") (pinfunction "LD_11") (pintype "input"))
      (node (ref "IC15") (pin "11") (pinfunction "O_11") (pintype "output"))
    )
    (net (code "140") (name "Net-(IC11A-QA)") (class "Default")
      (node (ref "IC11") (pin "3") (pinfunction "QA_3") (pintype "output"))
      (node (ref "IC14") (pin "11") (pinfunction "A1_11") (pintype "input"))
      (node (ref "IC18") (pin "2") (pinfunction "A1_2") (pintype "input"))
    )
    (net (code "141") (name "Net-(IC11A-QB)") (class "Default")
      (node (ref "IC11") (pin "2") (pinfunction "QB_2") (pintype "output"))
      (node (ref "IC14") (pin "13") (pinfunction "A2_13") (pintype "input"))
      (node (ref "IC18") (pin "4") (pinfunction "A2_4") (pintype "input"))
    )
    (net (code "142") (name "Net-(IC11A-QC)") (class "Default")
      (node (ref "IC11") (pin "6") (pinfunction "QC_6") (pintype "output"))
      (node (ref "IC14") (pin "15") (pinfunction "A3_15") (pintype "input"))
      (node (ref "IC18") (pin "6") (pinfunction "A3_6") (pintype "input"))
    )
    (net (code "143") (name "Net-(IC11A-QD)") (class "Default")
      (node (ref "IC11") (pin "7") (pinfunction "QD_7") (pintype "output"))
      (node (ref "IC14") (pin "17") (pinfunction "A4_17") (pintype "input"))
      (node (ref "IC18") (pin "8") (pinfunction "A4_8") (pintype "input"))
    )
    (net (code "144") (name "Net-(IC12A-QA)") (class "Default")
      (node (ref "IC12") (pin "3") (pinfunction "QA_3") (pintype "output"))
      (node (ref "IC14") (pin "2") (pinfunction "A1_2") (pintype "input"))
      (node (ref "IC18") (pin "11") (pinfunction "A1_11") (pintype "input"))
    )
    (net (code "145") (name "Net-(IC12A-QB)") (class "Default")
      (node (ref "IC12") (pin "2") (pinfunction "QB_2") (pintype "output"))
      (node (ref "IC14") (pin "4") (pinfunction "A2_4") (pintype "input"))
      (node (ref "IC18") (pin "13") (pinfunction "A2_13") (pintype "input"))
    )
    (net (code "146") (name "Net-(IC12A-QC)") (class "Default")
      (node (ref "IC12") (pin "6") (pinfunction "QC_6") (pintype "output"))
      (node (ref "IC14") (pin "6") (pinfunction "A3_6") (pintype "input"))
      (node (ref "IC18") (pin "15") (pinfunction "A3_15") (pintype "input"))
    )
    (net (code "147") (name "Net-(IC12A-QD)") (class "Default")
      (node (ref "IC12") (pin "7") (pinfunction "QD_7") (pintype "output"))
      (node (ref "IC14") (pin "8") (pinfunction "A4_8") (pintype "input"))
      (node (ref "IC18") (pin "17") (pinfunction "A4_17") (pintype "input"))
    )
    (net (code "148") (name "Net-(IC13A-G)") (class "Default")
      (node (ref "IC13") (pin "1") (pinfunction "G_1") (pintype "input"))
      (node (ref "IC13") (pin "19") (pinfunction "G_19") (pintype "input"))
      (node (ref "IC2") (pin "8") (pinfunction "O_8") (pintype "output"))
    )
    (net (code "149") (name "Net-(IC13B-A1)") (class "Default")
      (node (ref "IC13") (pin "11") (pinfunction "A1_11") (pintype "input"))
      (node (ref "IC17") (pin "2") (pinfunction "A1_2") (pintype "input"))
      (node (ref "IC9") (pin "3") (pinfunction "QA_3") (pintype "output"))
    )
    (net (code "150") (name "Net-(IC13B-A2)") (class "Default")
      (node (ref "IC13") (pin "13") (pinfunction "A2_13") (pintype "input"))
      (node (ref "IC17") (pin "4") (pinfunction "A2_4") (pintype "input"))
      (node (ref "IC9") (pin "2") (pinfunction "QB_2") (pintype "output"))
    )
    (net (code "151") (name "Net-(IC13B-A3)") (class "Default")
      (node (ref "IC13") (pin "15") (pinfunction "A3_15") (pintype "input"))
      (node (ref "IC17") (pin "6") (pinfunction "A3_6") (pintype "input"))
      (node (ref "IC9") (pin "6") (pinfunction "QC_6") (pintype "output"))
    )
    (net (code "152") (name "Net-(IC13B-A4)") (class "Default")
      (node (ref "IC13") (pin "17") (pinfunction "A4_17") (pintype "input"))
      (node (ref "IC17") (pin "8") (pinfunction "A4_8") (pintype "input"))
      (node (ref "IC9") (pin "7") (pinfunction "QD_7") (pintype "output"))
    )
    (net (code "153") (name "Net-(IC14A-G)") (class "Default")
      (node (ref "IC14") (pin "1") (pinfunction "G_1") (pintype "input"))
      (node (ref "IC14") (pin "19") (pinfunction "G_19") (pintype "input"))
      (node (ref "IC2") (pin "11") (pinfunction "O_11") (pintype "output"))
    )
    (net (code "154") (name "Net-(IC15A-O)") (class "Default")
      (node (ref "IC15") (pin "3") (pinfunction "O_3") (pintype "output"))
      (node (ref "IC9") (pin "5") (pinfunction "UP_5") (pintype "input"))
    )
    (net (code "155") (name "Net-(IC15B-O)") (class "Default")
      (node (ref "IC15") (pin "6") (pinfunction "O_6") (pintype "output"))
      (node (ref "IC9") (pin "4") (pinfunction "DN_4") (pintype "input"))
    )
    (net (code "156") (name "Net-(IC19A-BO)") (class "Default")
      (node (ref "IC19") (pin "13") (pinfunction "BO_13") (pintype "output"))
      (node (ref "IC20") (pin "4") (pinfunction "DN_4") (pintype "input"))
    )
    (net (code "157") (name "Net-(IC19A-CO)") (class "Default")
      (node (ref "IC19") (pin "12") (pinfunction "CO_12") (pintype "output"))
      (node (ref "IC20") (pin "5") (pinfunction "UP_5") (pintype "input"))
    )
    (net (code "158") (name "Net-(IC19A-DN)") (class "Default")
      (node (ref "IC19") (pin "4") (pinfunction "DN_4") (pintype "input"))
      (node (ref "IC25") (pin "6") (pinfunction "O_6") (pintype "output"))
    )
    (net (code "159") (name "Net-(IC19A-LD)") (class "Default")
      (node (ref "IC19") (pin "11") (pinfunction "LD_11") (pintype "input"))
      (node (ref "IC20") (pin "11") (pinfunction "LD_11") (pintype "input"))
      (node (ref "IC25") (pin "8") (pinfunction "O_8") (pintype "output"))
    )
    (net (code "160") (name "Net-(IC19A-QA)") (class "Default")
      (node (ref "IC19") (pin "3") (pinfunction "QA_3") (pintype "output"))
      (node (ref "IC23") (pin "11") (pinfunction "A1_11") (pintype "input"))
      (node (ref "IC27") (pin "2") (pinfunction "A1_2") (pintype "input"))
    )
    (net (code "161") (name "Net-(IC19A-QB)") (class "Default")
      (node (ref "IC19") (pin "2") (pinfunction "QB_2") (pintype "output"))
      (node (ref "IC23") (pin "13") (pinfunction "A2_13") (pintype "input"))
      (node (ref "IC27") (pin "4") (pinfunction "A2_4") (pintype "input"))
    )
    (net (code "162") (name "Net-(IC19A-QC)") (class "Default")
      (node (ref "IC19") (pin "6") (pinfunction "QC_6") (pintype "output"))
      (node (ref "IC23") (pin "15") (pinfunction "A3_15") (pintype "input"))
      (node (ref "IC27") (pin "6") (pinfunction "A3_6") (pintype "input"))
    )
    (net (code "163") (name "Net-(IC19A-QD)") (class "Default")
      (node (ref "IC19") (pin "7") (pinfunction "QD_7") (pintype "output"))
      (node (ref "IC23") (pin "17") (pinfunction "A4_17") (pintype "input"))
      (node (ref "IC27") (pin "8") (pinfunction "A4_8") (pintype "input"))
    )
    (net (code "164") (name "Net-(IC19A-UP)") (class "Default")
      (node (ref "IC19") (pin "5") (pinfunction "UP_5") (pintype "input"))
      (node (ref "IC25") (pin "3") (pinfunction "O_3") (pintype "output"))
    )
    (net (code "165") (name "Net-(IC20A-BO)") (class "Default")
      (node (ref "IC20") (pin "13") (pinfunction "BO_13") (pintype "output"))
      (node (ref "IC21") (pin "4") (pinfunction "DN_4") (pintype "input"))
    )
    (net (code "166") (name "Net-(IC20A-CO)") (class "Default")
      (node (ref "IC20") (pin "12") (pinfunction "CO_12") (pintype "output"))
      (node (ref "IC21") (pin "5") (pinfunction "UP_5") (pintype "input"))
    )
    (net (code "167") (name "Net-(IC20A-QA)") (class "Default")
      (node (ref "IC20") (pin "3") (pinfunction "QA_3") (pintype "output"))
      (node (ref "IC23") (pin "2") (pinfunction "A1_2") (pintype "input"))
      (node (ref "IC27") (pin "11") (pinfunction "A1_11") (pintype "input"))
    )
    (net (code "168") (name "Net-(IC20A-QB)") (class "Default")
      (node (ref "IC20") (pin "2") (pinfunction "QB_2") (pintype "output"))
      (node (ref "IC23") (pin "4") (pinfunction "A2_4") (pintype "input"))
      (node (ref "IC27") (pin "13") (pinfunction "A2_13") (pintype "input"))
    )
    (net (code "169") (name "Net-(IC20A-QC)") (class "Default")
      (node (ref "IC20") (pin "6") (pinfunction "QC_6") (pintype "output"))
      (node (ref "IC23") (pin "6") (pinfunction "A3_6") (pintype "input"))
      (node (ref "IC27") (pin "15") (pinfunction "A3_15") (pintype "input"))
    )
    (net (code "170") (name "Net-(IC20A-QD)") (class "Default")
      (node (ref "IC20") (pin "7") (pinfunction "QD_7") (pintype "output"))
      (node (ref "IC23") (pin "8") (pinfunction "A4_8") (pintype "input"))
      (node (ref "IC27") (pin "17") (pinfunction "A4_17") (pintype "input"))
    )
    (net (code "171") (name "Net-(IC21A-BO)") (class "Default")
      (node (ref "IC21") (pin "13") (pinfunction "BO_13") (pintype "output"))
      (node (ref "IC22") (pin "4") (pinfunction "DN_4") (pintype "input"))
    )
    (net (code "172") (name "Net-(IC21A-CO)") (class "Default")
      (node (ref "IC21") (pin "12") (pinfunction "CO_12") (pintype "output"))
      (node (ref "IC22") (pin "5") (pinfunction "UP_5") (pintype "input"))
    )
    (net (code "173") (name "Net-(IC21A-LD)") (class "Default")
      (node (ref "IC21") (pin "11") (pinfunction "LD_11") (pintype "input"))
      (node (ref "IC22") (pin "11") (pinfunction "LD_11") (pintype "input"))
      (node (ref "IC25") (pin "11") (pinfunction "O_11") (pintype "output"))
    )
    (net (code "174") (name "Net-(IC21A-QA)") (class "Default")
      (node (ref "IC21") (pin "3") (pinfunction "QA_3") (pintype "output"))
      (node (ref "IC24") (pin "11") (pinfunction "A1_11") (pintype "input"))
      (node (ref "IC28") (pin "2") (pinfunction "A1_2") (pintype "input"))
    )
    (net (code "175") (name "Net-(IC21A-QB)") (class "Default")
      (node (ref "IC21") (pin "2") (pinfunction "QB_2") (pintype "output"))
      (node (ref "IC24") (pin "13") (pinfunction "A2_13") (pintype "input"))
      (node (ref "IC28") (pin "4") (pinfunction "A2_4") (pintype "input"))
    )
    (net (code "176") (name "Net-(IC21A-QC)") (class "Default")
      (node (ref "IC21") (pin "6") (pinfunction "QC_6") (pintype "output"))
      (node (ref "IC24") (pin "15") (pinfunction "A3_15") (pintype "input"))
      (node (ref "IC28") (pin "6") (pinfunction "A3_6") (pintype "input"))
    )
    (net (code "177") (name "Net-(IC21A-QD)") (class "Default")
      (node (ref "IC21") (pin "7") (pinfunction "QD_7") (pintype "output"))
      (node (ref "IC24") (pin "17") (pinfunction "A4_17") (pintype "input"))
      (node (ref "IC28") (pin "8") (pinfunction "A4_8") (pintype "input"))
    )
    (net (code "178") (name "Net-(IC22A-QA)") (class "Default")
      (node (ref "IC22") (pin "3") (pinfunction "QA_3") (pintype "output"))
      (node (ref "IC24") (pin "2") (pinfunction "A1_2") (pintype "input"))
      (node (ref "IC28") (pin "11") (pinfunction "A1_11") (pintype "input"))
    )
    (net (code "179") (name "Net-(IC22A-QB)") (class "Default")
      (node (ref "IC22") (pin "2") (pinfunction "QB_2") (pintype "output"))
      (node (ref "IC24") (pin "4") (pinfunction "A2_4") (pintype "input"))
      (node (ref "IC28") (pin "13") (pinfunction "A2_13") (pintype "input"))
    )
    (net (code "180") (name "Net-(IC22A-QC)") (class "Default")
      (node (ref "IC22") (pin "6") (pinfunction "QC_6") (pintype "output"))
      (node (ref "IC24") (pin "6") (pinfunction "A3_6") (pintype "input"))
      (node (ref "IC28") (pin "15") (pinfunction "A3_15") (pintype "input"))
    )
    (net (code "181") (name "Net-(IC22A-QD)") (class "Default")
      (node (ref "IC22") (pin "7") (pinfunction "QD_7") (pintype "output"))
      (node (ref "IC24") (pin "8") (pinfunction "A4_8") (pintype "input"))
      (node (ref "IC28") (pin "17") (pinfunction "A4_17") (pintype "input"))
    )
    (net (code "182") (name "Net-(IC23A-G)") (class "Default")
      (node (ref "IC23") (pin "1") (pinfunction "G_1") (pintype "input"))
      (node (ref "IC23") (pin "19") (pinfunction "G_19") (pintype "input"))
      (node (ref "IC26") (pin "3") (pinfunction "O_3") (pintype "output"))
    )
    (net (code "183") (name "Net-(IC24A-G)") (class "Default")
      (node (ref "IC24") (pin "1") (pinfunction "G_1") (pintype "input"))
      (node (ref "IC24") (pin "19") (pinfunction "G_19") (pintype "input"))
      (node (ref "IC26") (pin "6") (pinfunction "O_6") (pintype "output"))
    )
    (net (code "184") (name "Net-(IC26C-O)") (class "Default")
      (node (ref "IC26") (pin "8") (pinfunction "O_8") (pintype "output"))
      (node (ref "IC45") (pin "1") (pinfunction "G_1") (pintype "input"))
      (node (ref "IC45") (pin "19") (pinfunction "G_19") (pintype "input"))
    )
    (net (code "185") (name "Net-(IC26D-O)") (class "Default")
      (node (ref "IC26") (pin "11") (pinfunction "O_11") (pintype "output"))
      (node (ref "IC46") (pin "1") (pinfunction "G_1") (pintype "input"))
      (node (ref "IC46") (pin "19") (pinfunction "G_19") (pintype "input"))
    )
    (net (code "186") (name "Net-(IC29A-BO)") (class "Default")
      (node (ref "IC29") (pin "13") (pinfunction "BO_13") (pintype "output"))
      (node (ref "IC30") (pin "4") (pinfunction "DN_4") (pintype "input"))
    )
    (net (code "187") (name "Net-(IC29A-CO)") (class "Default")
      (node (ref "IC29") (pin "12") (pinfunction "CO_12") (pintype "output"))
      (node (ref "IC30") (pin "5") (pinfunction "UP_5") (pintype "input"))
    )
    (net (code "188") (name "Net-(IC29A-DN)") (class "Default")
      (node (ref "IC29") (pin "4") (pinfunction "DN_4") (pintype "input"))
      (node (ref "IC47") (pin "6") (pinfunction "O_6") (pintype "output"))
    )
    (net (code "189") (name "Net-(IC29A-LD)") (class "Default")
      (node (ref "IC29") (pin "11") (pinfunction "LD_11") (pintype "input"))
      (node (ref "IC30") (pin "11") (pinfunction "LD_11") (pintype "input"))
      (node (ref "IC47") (pin "8") (pinfunction "O_8") (pintype "output"))
    )
    (net (code "190") (name "Net-(IC29A-QA)") (class "Default")
      (node (ref "IC29") (pin "3") (pinfunction "QA_3") (pintype "output"))
      (node (ref "IC45") (pin "11") (pinfunction "A1_11") (pintype "input"))
      (node (ref "IC49") (pin "2") (pinfunction "A1_2") (pintype "input"))
    )
    (net (code "191") (name "Net-(IC29A-QB)") (class "Default")
      (node (ref "IC29") (pin "2") (pinfunction "QB_2") (pintype "output"))
      (node (ref "IC45") (pin "13") (pinfunction "A2_13") (pintype "input"))
      (node (ref "IC49") (pin "4") (pinfunction "A2_4") (pintype "input"))
    )
    (net (code "192") (name "Net-(IC29A-QC)") (class "Default")
      (node (ref "IC29") (pin "6") (pinfunction "QC_6") (pintype "output"))
      (node (ref "IC45") (pin "15") (pinfunction "A3_15") (pintype "input"))
      (node (ref "IC49") (pin "6") (pinfunction "A3_6") (pintype "input"))
    )
    (net (code "193") (name "Net-(IC29A-QD)") (class "Default")
      (node (ref "IC29") (pin "7") (pinfunction "QD_7") (pintype "output"))
      (node (ref "IC45") (pin "17") (pinfunction "A4_17") (pintype "input"))
      (node (ref "IC49") (pin "8") (pinfunction "A4_8") (pintype "input"))
    )
    (net (code "194") (name "Net-(IC29A-UP)") (class "Default")
      (node (ref "IC29") (pin "5") (pinfunction "UP_5") (pintype "input"))
      (node (ref "IC47") (pin "3") (pinfunction "O_3") (pintype "output"))
    )
    (net (code "195") (name "Net-(IC30A-BO)") (class "Default")
      (node (ref "IC30") (pin "13") (pinfunction "BO_13") (pintype "output"))
      (node (ref "IC43") (pin "4") (pinfunction "DN_4") (pintype "input"))
    )
    (net (code "196") (name "Net-(IC30A-CO)") (class "Default")
      (node (ref "IC30") (pin "12") (pinfunction "CO_12") (pintype "output"))
      (node (ref "IC43") (pin "5") (pinfunction "UP_5") (pintype "input"))
    )
    (net (code "197") (name "Net-(IC30A-QA)") (class "Default")
      (node (ref "IC30") (pin "3") (pinfunction "QA_3") (pintype "output"))
      (node (ref "IC45") (pin "2") (pinfunction "A1_2") (pintype "input"))
      (node (ref "IC49") (pin "11") (pinfunction "A1_11") (pintype "input"))
    )
    (net (code "198") (name "Net-(IC30A-QB)") (class "Default")
      (node (ref "IC30") (pin "2") (pinfunction "QB_2") (pintype "output"))
      (node (ref "IC45") (pin "4") (pinfunction "A2_4") (pintype "input"))
      (node (ref "IC49") (pin "13") (pinfunction "A2_13") (pintype "input"))
    )
    (net (code "199") (name "Net-(IC30A-QC)") (class "Default")
      (node (ref "IC30") (pin "6") (pinfunction "QC_6") (pintype "output"))
      (node (ref "IC45") (pin "6") (pinfunction "A3_6") (pintype "input"))
      (node (ref "IC49") (pin "15") (pinfunction "A3_15") (pintype "input"))
    )
    (net (code "200") (name "Net-(IC30A-QD)") (class "Default")
      (node (ref "IC30") (pin "7") (pinfunction "QD_7") (pintype "output"))
      (node (ref "IC45") (pin "8") (pinfunction "A4_8") (pintype "input"))
      (node (ref "IC49") (pin "17") (pinfunction "A4_17") (pintype "input"))
    )
    (net (code "201") (name "Net-(IC31A-O)") (class "Default")
      (node (ref "IC31") (pin "3") (pinfunction "O_3") (pintype "output"))
      (node (ref "IC32") (pin "1") (pinfunction "G_1") (pintype "input"))
    )
    (net (code "202") (name "Net-(IC31B-O)") (class "Default")
      (node (ref "IC31") (pin "6") (pinfunction "O_6") (pintype "output"))
      (node (ref "IC32") (pin "15") (pinfunction "G_15") (pintype "input"))
    )
    (net (code "203") (name "Net-(IC31C-I0)") (class "Default")
      (node (ref "IC31") (pin "9") (pinfunction "I0_9") (pintype "input"))
      (node (ref "IC34") (pin "10") (pinfunction "O_10") (pintype "output"))
    )
    (net (code "204") (name "Net-(IC31C-I1)") (class "Default")
      (node (ref "IC31") (pin "10") (pinfunction "I1_10") (pintype "input"))
      (node (ref "IC31") (pin "12") (pinfunction "I0_12") (pintype "input"))
      (node (ref "IC34") (pin "11") (pinfunction "O_11") (pintype "output"))
    )
    (net (code "205") (name "Net-(IC31C-O)") (class "Default")
      (node (ref "IC31") (pin "8") (pinfunction "O_8") (pintype "output"))
      (node (ref "IC35") (pin "19") (pinfunction "G_19") (pintype "input"))
      (node (ref "IC36") (pin "19") (pinfunction "G_19") (pintype "input"))
    )
    (net (code "206") (name "Net-(IC31D-O)") (class "Default")
      (node (ref "IC31") (pin "11") (pinfunction "O_11") (pintype "output"))
      (node (ref "IC37") (pin "19") (pinfunction "G_19") (pintype "input"))
    )
    (net (code "207") (name "Net-(IC32A-Y1)") (class "Default")
      (node (ref "IC32") (pin "5") (pinfunction "Y1_5") (pintype "output"))
      (node (ref "J1") (pin "3") (pinfunction "3_3") (pintype "passive"))
    )
    (net (code "208") (name "Net-(IC32A-Y2)") (class "Default")
      (node (ref "IC32") (pin "6") (pinfunction "Y2_6") (pintype "output"))
      (node (ref "J1") (pin "5") (pinfunction "5_5") (pintype "passive"))
    )
    (net (code "209") (name "Net-(IC32A-Y3)") (class "Default")
      (node (ref "IC32") (pin "7") (pinfunction "Y3_7") (pintype "output"))
      (node (ref "J1") (pin "7") (pinfunction "7_7") (pintype "passive"))
    )
    (net (code "210") (name "Net-(IC32B-Y1)") (class "Default")
      (node (ref "IC32") (pin "11") (pinfunction "Y1_11") (pintype "output"))
      (node (ref "J2") (pin "3") (pinfunction "3_3") (pintype "passive"))
    )
    (net (code "211") (name "Net-(IC32B-Y2)") (class "Default")
      (node (ref "IC32") (pin "10") (pinfunction "Y2_10") (pintype "output"))
      (node (ref "J2") (pin "5") (pinfunction "5_5") (pintype "passive"))
    )
    (net (code "212") (name "Net-(IC32B-Y3)") (class "Default")
      (node (ref "IC32") (pin "9") (pinfunction "Y3_9") (pintype "output"))
      (node (ref "J2") (pin "7") (pinfunction "7_7") (pintype "passive"))
    )
    (net (code "213") (name "Net-(IC38B-G)") (class "Default")
      (node (ref "IC38") (pin "15") (pinfunction "G_15") (pintype "input"))
      (node (ref "IC40") (pin "3") (pinfunction "O_3") (pintype "output"))
    )
    (net (code "214") (name "Net-(IC38B-Y1)") (class "Default")
      (node (ref "IC38") (pin "11") (pinfunction "Y1_11") (pintype "output"))
      (node (ref "J3") (pin "3") (pinfunction "3_3") (pintype "passive"))
    )
    (net (code "215") (name "Net-(IC38B-Y2)") (class "Default")
      (node (ref "IC38") (pin "10") (pinfunction "Y2_10") (pintype "output"))
      (node (ref "J3") (pin "5") (pinfunction "5_5") (pintype "passive"))
    )
    (net (code "216") (name "Net-(IC38B-Y3)") (class "Default")
      (node (ref "IC38") (pin "9") (pinfunction "Y3_9") (pintype "output"))
      (node (ref "J3") (pin "7") (pinfunction "7_7") (pintype "passive"))
    )
    (net (code "217") (name "Net-(IC41B-A1)") (class "Default")
      (node (ref "IC4") (pin "3") (pinfunction "QA_3") (pintype "output"))
      (node (ref "IC41") (pin "11") (pinfunction "A1_11") (pintype "input"))
      (node (ref "IC7") (pin "2") (pinfunction "A1_2") (pintype "input"))
    )
    (net (code "218") (name "Net-(IC41B-A2)") (class "Default")
      (node (ref "IC4") (pin "2") (pinfunction "QB_2") (pintype "output"))
      (node (ref "IC41") (pin "13") (pinfunction "A2_13") (pintype "input"))
      (node (ref "IC7") (pin "4") (pinfunction "A2_4") (pintype "input"))
    )
    (net (code "219") (name "Net-(IC41B-A3)") (class "Default")
      (node (ref "IC4") (pin "6") (pinfunction "QC_6") (pintype "output"))
      (node (ref "IC41") (pin "15") (pinfunction "A3_15") (pintype "input"))
      (node (ref "IC7") (pin "6") (pinfunction "A3_6") (pintype "input"))
    )
    (net (code "220") (name "Net-(IC41B-A4)") (class "Default")
      (node (ref "IC4") (pin "7") (pinfunction "QD_7") (pintype "output"))
      (node (ref "IC41") (pin "17") (pinfunction "A4_17") (pintype "input"))
      (node (ref "IC7") (pin "8") (pinfunction "A4_8") (pintype "input"))
    )
    (net (code "221") (name "Net-(IC42A-A1)") (class "Default")
      (node (ref "IC42") (pin "2") (pinfunction "A1_2") (pintype "input"))
      (node (ref "IC5") (pin "3") (pinfunction "QA_3") (pintype "output"))
      (node (ref "IC8") (pin "11") (pinfunction "A1_11") (pintype "input"))
    )
    (net (code "222") (name "Net-(IC42A-A2)") (class "Default")
      (node (ref "IC42") (pin "4") (pinfunction "A2_4") (pintype "input"))
      (node (ref "IC5") (pin "2") (pinfunction "QB_2") (pintype "output"))
      (node (ref "IC8") (pin "13") (pinfunction "A2_13") (pintype "input"))
    )
    (net (code "223") (name "Net-(IC42A-A3)") (class "Default")
      (node (ref "IC42") (pin "6") (pinfunction "A3_6") (pintype "input"))
      (node (ref "IC5") (pin "6") (pinfunction "QC_6") (pintype "output"))
      (node (ref "IC8") (pin "15") (pinfunction "A3_15") (pintype "input"))
    )
    (net (code "224") (name "Net-(IC42A-A4)") (class "Default")
      (node (ref "IC42") (pin "8") (pinfunction "A4_8") (pintype "input"))
      (node (ref "IC5") (pin "7") (pinfunction "QD_7") (pintype "output"))
      (node (ref "IC8") (pin "17") (pinfunction "A4_17") (pintype "input"))
    )
    (net (code "225") (name "Net-(IC42B-A1)") (class "Default")
      (node (ref "IC42") (pin "11") (pinfunction "A1_11") (pintype "input"))
      (node (ref "IC6") (pin "3") (pinfunction "QA_3") (pintype "output"))
      (node (ref "IC8") (pin "2") (pinfunction "A1_2") (pintype "input"))
    )
    (net (code "226") (name "Net-(IC42B-A2)") (class "Default")
      (node (ref "IC42") (pin "13") (pinfunction "A2_13") (pintype "input"))
      (node (ref "IC6") (pin "2") (pinfunction "QB_2") (pintype "output"))
      (node (ref "IC8") (pin "4") (pinfunction "A2_4") (pintype "input"))
    )
    (net (code "227") (name "Net-(IC42B-A3)") (class "Default")
      (node (ref "IC42") (pin "15") (pinfunction "A3_15") (pintype "input"))
      (node (ref "IC6") (pin "6") (pinfunction "QC_6") (pintype "output"))
      (node (ref "IC8") (pin "6") (pinfunction "A3_6") (pintype "input"))
    )
    (net (code "228") (name "Net-(IC42B-A4)") (class "Default")
      (node (ref "IC42") (pin "17") (pinfunction "A4_17") (pintype "input"))
      (node (ref "IC6") (pin "7") (pinfunction "QD_7") (pintype "output"))
      (node (ref "IC8") (pin "8") (pinfunction "A4_8") (pintype "input"))
    )
    (net (code "229") (name "Net-(IC43A-BO)") (class "Default")
      (node (ref "IC43") (pin "13") (pinfunction "BO_13") (pintype "output"))
      (node (ref "IC44") (pin "4") (pinfunction "DN_4") (pintype "input"))
    )
    (net (code "230") (name "Net-(IC43A-CO)") (class "Default")
      (node (ref "IC43") (pin "12") (pinfunction "CO_12") (pintype "output"))
      (node (ref "IC44") (pin "5") (pinfunction "UP_5") (pintype "input"))
    )
    (net (code "231") (name "Net-(IC43A-LD)") (class "Default")
      (node (ref "IC43") (pin "11") (pinfunction "LD_11") (pintype "input"))
      (node (ref "IC44") (pin "11") (pinfunction "LD_11") (pintype "input"))
      (node (ref "IC47") (pin "11") (pinfunction "O_11") (pintype "output"))
    )
    (net (code "232") (name "Net-(IC43A-QA)") (class "Default")
      (node (ref "IC43") (pin "3") (pinfunction "QA_3") (pintype "output"))
      (node (ref "IC46") (pin "11") (pinfunction "A1_11") (pintype "input"))
      (node (ref "IC50") (pin "2") (pinfunction "A1_2") (pintype "input"))
    )
    (net (code "233") (name "Net-(IC43A-QB)") (class "Default")
      (node (ref "IC43") (pin "2") (pinfunction "QB_2") (pintype "output"))
      (node (ref "IC46") (pin "13") (pinfunction "A2_13") (pintype "input"))
      (node (ref "IC50") (pin "4") (pinfunction "A2_4") (pintype "input"))
    )
    (net (code "234") (name "Net-(IC43A-QC)") (class "Default")
      (node (ref "IC43") (pin "6") (pinfunction "QC_6") (pintype "output"))
      (node (ref "IC46") (pin "15") (pinfunction "A3_15") (pintype "input"))
      (node (ref "IC50") (pin "6") (pinfunction "A3_6") (pintype "input"))
    )
    (net (code "235") (name "Net-(IC43A-QD)") (class "Default")
      (node (ref "IC43") (pin "7") (pinfunction "QD_7") (pintype "output"))
      (node (ref "IC46") (pin "17") (pinfunction "A4_17") (pintype "input"))
      (node (ref "IC50") (pin "8") (pinfunction "A4_8") (pintype "input"))
    )
    (net (code "236") (name "Net-(IC44A-QA)") (class "Default")
      (node (ref "IC44") (pin "3") (pinfunction "QA_3") (pintype "output"))
      (node (ref "IC46") (pin "2") (pinfunction "A1_2") (pintype "input"))
      (node (ref "IC50") (pin "11") (pinfunction "A1_11") (pintype "input"))
    )
    (net (code "237") (name "Net-(IC44A-QB)") (class "Default")
      (node (ref "IC44") (pin "2") (pinfunction "QB_2") (pintype "output"))
      (node (ref "IC46") (pin "4") (pinfunction "A2_4") (pintype "input"))
      (node (ref "IC50") (pin "13") (pinfunction "A2_13") (pintype "input"))
    )
    (net (code "238") (name "Net-(IC44A-QC)") (class "Default")
      (node (ref "IC44") (pin "6") (pinfunction "QC_6") (pintype "output"))
      (node (ref "IC46") (pin "6") (pinfunction "A3_6") (pintype "input"))
      (node (ref "IC50") (pin "15") (pinfunction "A3_15") (pintype "input"))
    )
    (net (code "239") (name "Net-(IC44A-QD)") (class "Default")
      (node (ref "IC44") (pin "7") (pinfunction "QD_7") (pintype "output"))
      (node (ref "IC46") (pin "8") (pinfunction "A4_8") (pintype "input"))
      (node (ref "IC50") (pin "17") (pinfunction "A4_17") (pintype "input"))
    )
    (net (code "240") (name "Net-(PWR-PadA)") (class "Default")
      (node (ref "PWR") (pin "A") (pinfunction "A_A") (pintype "passive"))
      (node (ref "R1") (pin "1") (pinfunction "1_1") (pintype "passive"))
    )
    (net (code "241") (name "OUT") (class "Default")
      (node (ref "X1") (pin "C27") (pinfunction "B_C27") (pintype "passive"))
    )
    (net (code "242") (name "REG-LD-ID0") (class "Default")
      (node (ref "IC33") (pin "14") (pinfunction "A_14") (pintype "input"))
      (node (ref "X1") (pin "B13") (pinfunction "B_B13") (pintype "passive"))
    )
    (net (code "243") (name "REG-LD-ID1") (class "Default")
      (node (ref "IC33") (pin "13") (pinfunction "B_13") (pintype "input"))
      (node (ref "X1") (pin "B14") (pinfunction "B_B14") (pintype "passive"))
    )
    (net (code "244") (name "REG-LD-ID2") (class "Default")
      (node (ref "IC32") (pin "14") (pinfunction "A_14") (pintype "input"))
      (node (ref "X1") (pin "B15") (pinfunction "B_B15") (pintype "passive"))
    )
    (net (code "245") (name "REG-LD-ID3") (class "Default")
      (node (ref "IC32") (pin "13") (pinfunction "B_13") (pintype "input"))
      (node (ref "X1") (pin "B16") (pinfunction "B_B16") (pintype "passive"))
    )
    (net (code "246") (name "REG-RD-ID0") (class "Default")
      (node (ref "IC33") (pin "2") (pinfunction "A_2") (pintype "input"))
      (node (ref "X1") (pin "B9") (pinfunction "B_B9") (pintype "passive"))
    )
    (net (code "247") (name "REG-RD-ID1") (class "Default")
      (node (ref "IC33") (pin "3") (pinfunction "B_3") (pintype "input"))
      (node (ref "X1") (pin "B10") (pinfunction "B_B10") (pintype "passive"))
    )
    (net (code "248") (name "REG-RD-ID2") (class "Default")
      (node (ref "IC32") (pin "2") (pinfunction "A_2") (pintype "input"))
      (node (ref "X1") (pin "B11") (pinfunction "B_B11") (pintype "passive"))
    )
    (net (code "249") (name "REG-RD-ID3") (class "Default")
      (node (ref "IC32") (pin "3") (pinfunction "B_3") (pintype "input"))
      (node (ref "X1") (pin "B12") (pinfunction "B_B12") (pintype "passive"))
    )
    (net (code "250") (name "RESET") (class "Default")
      (node (ref "IC10") (pin "14") (pinfunction "CLR_14") (pintype "input"))
      (node (ref "IC11") (pin "14") (pinfunction "CLR_14") (pintype "input"))
      (node (ref "IC12") (pin "14") (pinfunction "CLR_14") (pintype "input"))
      (node (ref "IC19") (pin "14") (pinfunction "CLR_14") (pintype "input"))
      (node (ref "IC20") (pin "14") (pinfunction "CLR_14") (pintype "input"))
      (node (ref "IC21") (pin "14") (pinfunction "CLR_14") (pintype "input"))
      (node (ref "IC22") (pin "14") (pinfunction "CLR_14") (pintype "input"))
      (node (ref "IC29") (pin "14") (pinfunction "CLR_14") (pintype "input"))
      (node (ref "IC3") (pin "14") (pinfunction "CLR_14") (pintype "input"))
      (node (ref "IC30") (pin "14") (pinfunction "CLR_14") (pintype "input"))
      (node (ref "IC34") (pin "3") (pinfunction "O_3") (pintype "output"))
      (node (ref "IC4") (pin "14") (pinfunction "CLR_14") (pintype "input"))
      (node (ref "IC43") (pin "14") (pinfunction "CLR_14") (pintype "input"))
      (node (ref "IC44") (pin "14") (pinfunction "CLR_14") (pintype "input"))
      (node (ref "IC5") (pin "14") (pinfunction "CLR_14") (pintype "input"))
      (node (ref "IC6") (pin "14") (pinfunction "CLR_14") (pintype "input"))
      (node (ref "IC9") (pin "14") (pinfunction "CLR_14") (pintype "input"))
    )
    (net (code "251") (name "VCC") (class "Default")
      (node (ref "C1") (pin "1") (pinfunction "1_1") (pintype "passive"))
      (node (ref "C10") (pin "1") (pinfunction "1_1") (pintype "passive"))
      (node (ref "C11") (pin "1") (pinfunction "1_1") (pintype "passive"))
      (node (ref "C12") (pin "1") (pinfunction "1_1") (pintype "passive"))
      (node (ref "C13") (pin "1") (pinfunction "1_1") (pintype "passive"))
      (node (ref "C14") (pin "1") (pinfunction "1_1") (pintype "passive"))
      (node (ref "C15") (pin "1") (pinfunction "1_1") (pintype "passive"))
      (node (ref "C16") (pin "1") (pinfunction "1_1") (pintype "passive"))
      (node (ref "C17") (pin "1") (pinfunction "1_1") (pintype "passive"))
      (node (ref "C18") (pin "1") (pinfunction "1_1") (pintype "passive"))
      (node (ref "C19") (pin "1") (pinfunction "1_1") (pintype "passive"))
      (node (ref "C2") (pin "1") (pinfunction "1_1") (pintype "passive"))
      (node (ref "C20") (pin "1") (pinfunction "1_1") (pintype "passive"))
      (node (ref "C21") (pin "1") (pinfunction "1_1") (pintype "passive"))
      (node (ref "C22") (pin "1") (pinfunction "1_1") (pintype "passive"))
      (node (ref "C23") (pin "1") (pinfunction "1_1") (pintype "passive"))
      (node (ref "C24") (pin "1") (pinfunction "1_1") (pintype "passive"))
      (node (ref "C25") (pin "1") (pinfunction "1_1") (pintype "passive"))
      (node (ref "C26") (pin "1") (pinfunction "1_1") (pintype "passive"))
      (node (ref "C27") (pin "1") (pinfunction "1_1") (pintype "passive"))
      (node (ref "C28") (pin "1") (pinfunction "1_1") (pintype "passive"))
      (node (ref "C29") (pin "1") (pinfunction "1_1") (pintype "passive"))
      (node (ref "C3") (pin "1") (pinfunction "1_1") (pintype "passive"))
      (node (ref "C30") (pin "1") (pinfunction "1_1") (pintype "passive"))
      (node (ref "C31") (pin "1") (pinfunction "1_1") (pintype "passive"))
      (node (ref "C32") (pin "1") (pinfunction "1_1") (pintype "passive"))
      (node (ref "C33") (pin "1") (pinfunction "1_1") (pintype "passive"))
      (node (ref "C34") (pin "1") (pinfunction "1_1") (pintype "passive"))
      (node (ref "C35") (pin "1") (pinfunction "1_1") (pintype "passive"))
      (node (ref "C36") (pin "1") (pinfunction "1_1") (pintype "passive"))
      (node (ref "C37") (pin "1") (pinfunction "1_1") (pintype "passive"))
      (node (ref "C38") (pin "1") (pinfunction "1_1") (pintype "passive"))
      (node (ref "C4") (pin "1") (pinfunction "1_1") (pintype "passive"))
      (node (ref "C5") (pin "1") (pinfunction "1_1") (pintype "passive"))
      (node (ref "C6") (pin "1") (pinfunction "1_1") (pintype "passive"))
      (node (ref "C8") (pin "1") (pinfunction "1_1") (pintype "passive"))
      (node (ref "C9") (pin "1") (pinfunction "1_1") (pintype "passive"))
      (node (ref "R1") (pin "2") (pinfunction "2_2") (pintype "passive"))
      (node (ref "RN1") (pin "1") (pinfunction "1_1") (pintype "passive"))
      (node (ref "RN2") (pin "1") (pinfunction "1_1") (pintype "passive"))
      (node (ref "X1") (pin "A2") (pinfunction "B_A2") (pintype "passive"))
      (node (ref "X1") (pin "A31") (pinfunction "B_A31") (pintype "passive"))
      (node (ref "X1") (pin "B2") (pinfunction "B_B2") (pintype "passive"))
      (node (ref "X1") (pin "B31") (pinfunction "B_B31") (pintype "passive"))
      (node (ref "X1") (pin "C2") (pinfunction "B_C2") (pintype "passive"))
      (node (ref "X1") (pin "C31") (pinfunction "B_C31") (pintype "passive"))
    )
    (net (code "252") (name "unconnected-(IC6A-BO-Pad13)") (class "Default")
      (node (ref "IC6") (pin "13") (pinfunction "BO_13") (pintype "output"))
    )
    (net (code "253") (name "unconnected-(IC6A-CO-Pad12)") (class "Default")
      (node (ref "IC6") (pin "12") (pinfunction "CO_12") (pintype "output"))
    )
    (net (code "254") (name "unconnected-(IC12A-BO-Pad13)") (class "Default")
      (node (ref "IC12") (pin "13") (pinfunction "BO_13") (pintype "output"))
    )
    (net (code "255") (name "unconnected-(IC12A-CO-Pad12)") (class "Default")
      (node (ref "IC12") (pin "12") (pinfunction "CO_12") (pintype "output"))
    )
    (net (code "256") (name "unconnected-(IC22A-BO-Pad13)") (class "Default")
      (node (ref "IC22") (pin "13") (pinfunction "BO_13") (pintype "output"))
    )
    (net (code "257") (name "unconnected-(IC22A-CO-Pad12)") (class "Default")
      (node (ref "IC22") (pin "12") (pinfunction "CO_12") (pintype "output"))
    )
    (net (code "258") (name "unconnected-(IC44A-BO-Pad13)") (class "Default")
      (node (ref "IC44") (pin "13") (pinfunction "BO_13") (pintype "output"))
    )
    (net (code "259") (name "unconnected-(IC44A-CO-Pad12)") (class "Default")
      (node (ref "IC44") (pin "12") (pinfunction "CO_12") (pintype "output"))
    )
  )
)
